# OBC_My_FPGA.net
KiCad netlist of a schematic drawn in Altium Designer
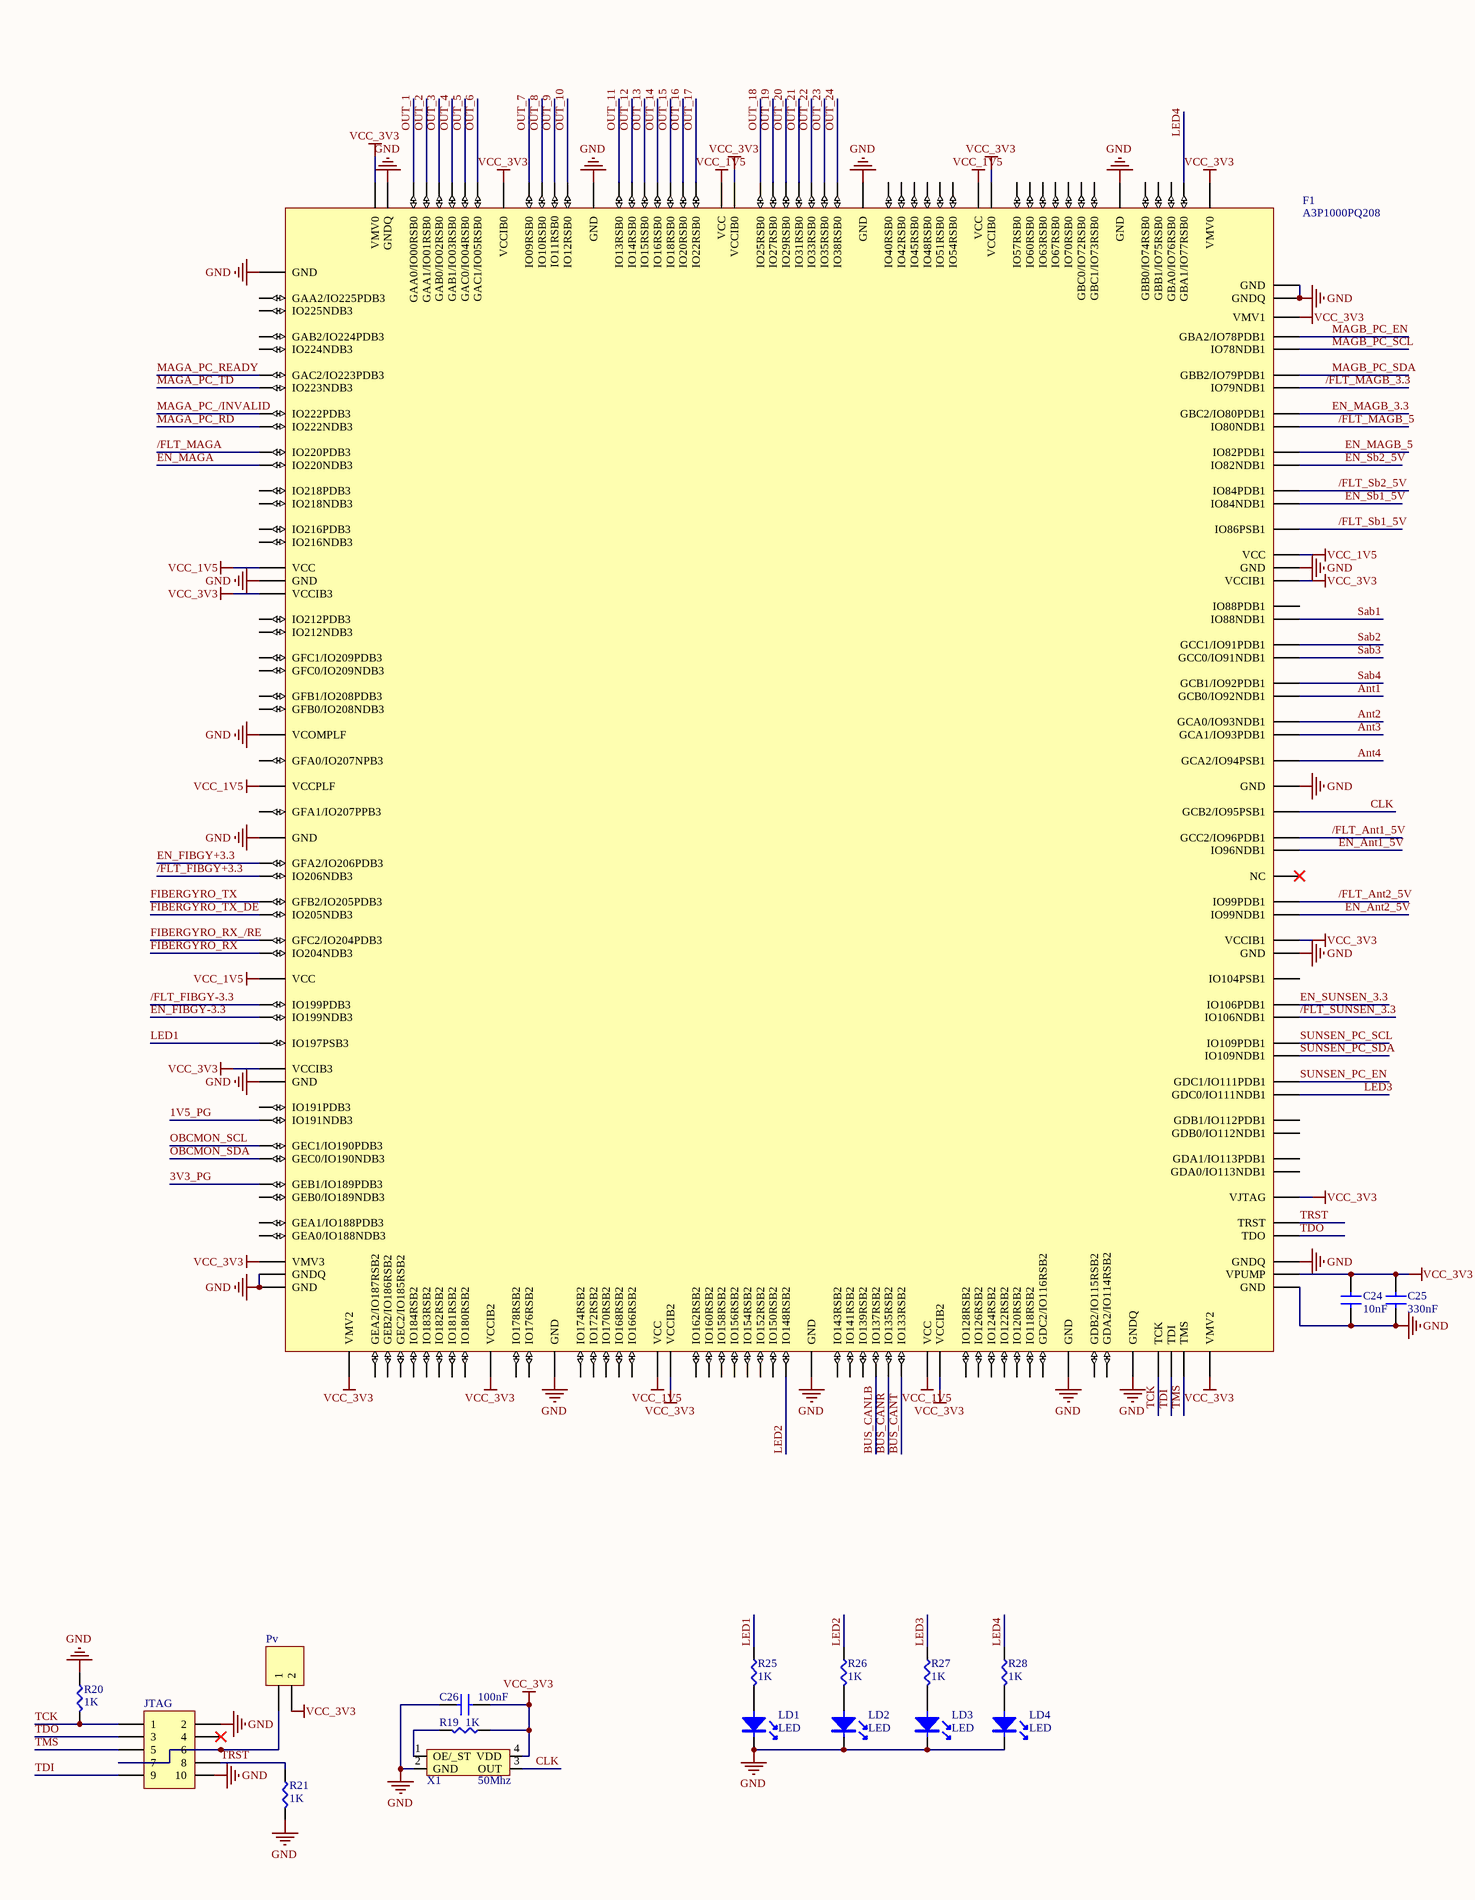
[diagram p0: OBC_My_FPGA.SchDoc, left]
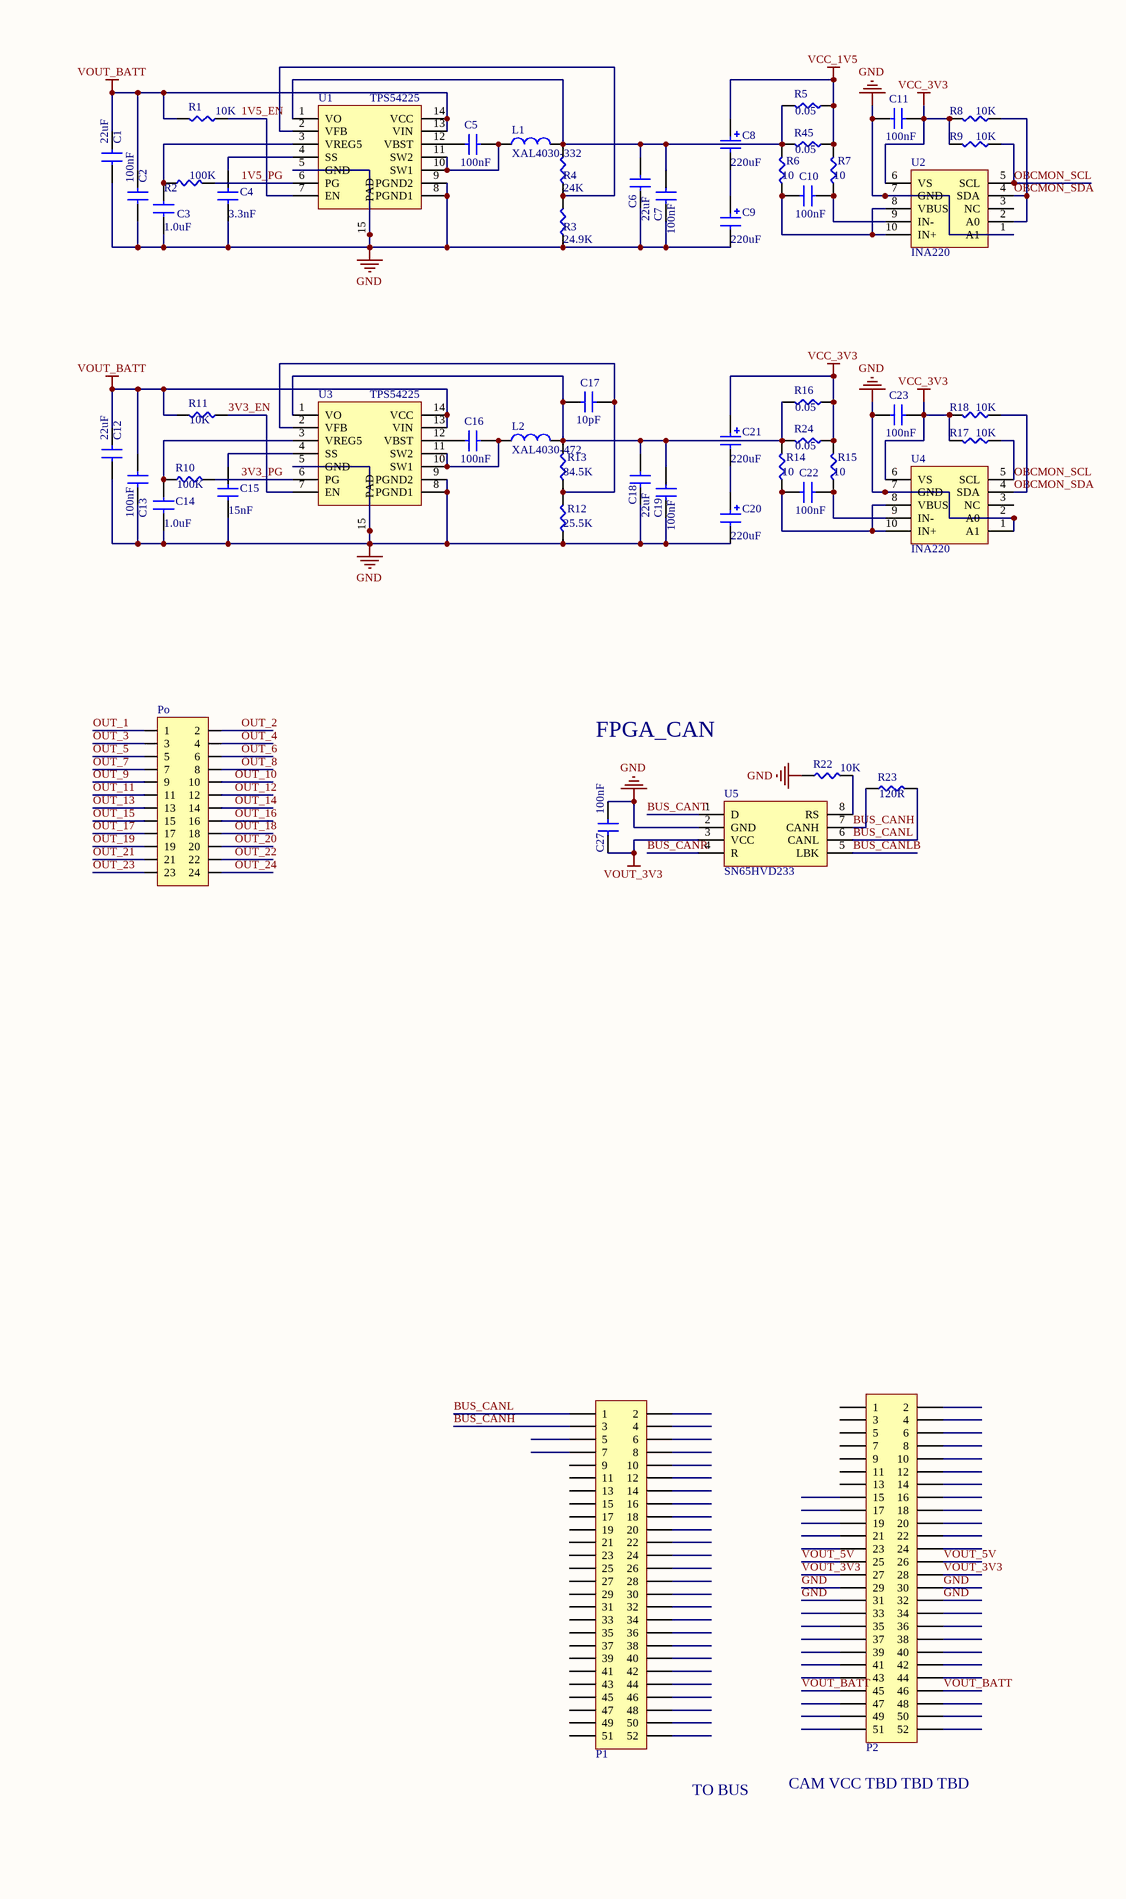
[diagram p1: OBC_My_FPGA.SchDoc, right]

(export (version "E")
  (design (tool "Eeschema 10.0.6"))
  (components
    (comp (ref "C1")
      (value "22uF")
      (footprint "1210(3225)-C-IPC")
      (description "Nonpolarized Capacitor (Surface Mount)")
      (libsource (lib "General Components") (part "Cap_1"))
    )
    (comp (ref "C2")
      (value "100nF")
      (footprint "0805(2012)-C-IPC")
      (description "Nonpolarized Capacitor (Surface Mount)")
      (libsource (lib "General Components") (part "Cap_1"))
    )
    (comp (ref "C3")
      (value "1.0uF")
      (footprint "0603(1608)-C-IPC")
      (description "Nonpolarized Capacitor (Surface Mount)")
      (libsource (lib "General Components") (part "Cap_1"))
    )
    (comp (ref "C4")
      (value "3.3nF")
      (footprint "0603(1608)-C-IPC")
      (description "Nonpolarized Capacitor (Surface Mount)")
      (libsource (lib "General Components") (part "Cap_1"))
    )
    (comp (ref "C5")
      (value "100nF")
      (footprint "0603(1608)-C-IPC")
      (description "Nonpolarized Capacitor (Surface Mount)")
      (libsource (lib "General Components") (part "Cap_1"))
    )
    (comp (ref "C6")
      (value "22uF")
      (footprint "1210(3225)-C-IPC")
      (description "Nonpolarized Capacitor (Surface Mount)")
      (libsource (lib "General Components") (part "Cap_1"))
    )
    (comp (ref "C7")
      (value "100nF")
      (footprint "0805(2012)-C-IPC")
      (description "Nonpolarized Capacitor (Surface Mount)")
      (libsource (lib "General Components") (part "Cap_1"))
    )
    (comp (ref "C8")
      (value "220uF")
      (footprint "TanCap-D(7343)-C-IPC")
      (description "Polarized Capacitor (Surface Mount)")
      (libsource (lib "General Components") (part "Cap Pol_1"))
    )
    (comp (ref "C9")
      (value "220uF")
      (footprint "TanCap-D(7343)-C-IPC")
      (description "Polarized Capacitor (Surface Mount)")
      (libsource (lib "General Components") (part "Cap Pol_1"))
    )
    (comp (ref "C10")
      (value "100nF")
      (footprint "0603(1608)-C-IPC")
      (description "Nonpolarized Capacitor (Surface Mount)")
      (libsource (lib "General Components") (part "Cap_1"))
    )
    (comp (ref "C11")
      (value "100nF")
      (footprint "0603(1608)-C-IPC")
      (description "Nonpolarized Capacitor (Surface Mount)")
      (libsource (lib "General Components") (part "Cap_1"))
    )
    (comp (ref "C12")
      (value "22uF")
      (footprint "1210(3225)-C-IPC")
      (description "Nonpolarized Capacitor (Surface Mount)")
      (libsource (lib "General Components") (part "Cap_1"))
    )
    (comp (ref "C13")
      (value "100nF")
      (footprint "0805(2012)-C-IPC")
      (description "Nonpolarized Capacitor (Surface Mount)")
      (libsource (lib "General Components") (part "Cap_1"))
    )
    (comp (ref "C14")
      (value "1.0uF")
      (footprint "0603(1608)-C-IPC")
      (description "Nonpolarized Capacitor (Surface Mount)")
      (libsource (lib "General Components") (part "Cap_1"))
    )
    (comp (ref "C15")
      (value "15nF")
      (footprint "0603(1608)-C-IPC")
      (description "Nonpolarized Capacitor (Surface Mount)")
      (libsource (lib "General Components") (part "Cap_1"))
    )
    (comp (ref "C16")
      (value "100nF")
      (footprint "0603(1608)-C-IPC")
      (description "Nonpolarized Capacitor (Surface Mount)")
      (libsource (lib "General Components") (part "Cap_1"))
    )
    (comp (ref "C17")
      (value "10pF")
      (footprint "0603(1608)-C-IPC")
      (description "Nonpolarized Capacitor (Surface Mount)")
      (libsource (lib "General Components") (part "Cap_1"))
    )
    (comp (ref "C18")
      (value "22uF")
      (footprint "1210(3225)-C-IPC")
      (description "Nonpolarized Capacitor (Surface Mount)")
      (libsource (lib "General Components") (part "Cap_1"))
    )
    (comp (ref "C19")
      (value "100nF")
      (footprint "0805(2012)-C-IPC")
      (description "Nonpolarized Capacitor (Surface Mount)")
      (libsource (lib "General Components") (part "Cap_1"))
    )
    (comp (ref "C20")
      (value "220uF")
      (footprint "TanCap-D(7343)-C-IPC")
      (description "Polarized Capacitor (Surface Mount)")
      (libsource (lib "General Components") (part "Cap Pol_1"))
    )
    (comp (ref "C21")
      (value "220uF")
      (footprint "TanCap-D(7343)-C-IPC")
      (description "Polarized Capacitor (Surface Mount)")
      (libsource (lib "General Components") (part "Cap Pol_1"))
    )
    (comp (ref "C22")
      (value "100nF")
      (footprint "0603(1608)-C-IPC")
      (description "Nonpolarized Capacitor (Surface Mount)")
      (libsource (lib "General Components") (part "Cap_1"))
    )
    (comp (ref "C23")
      (value "100nF")
      (footprint "0603(1608)-C-IPC")
      (description "Nonpolarized Capacitor (Surface Mount)")
      (libsource (lib "General Components") (part "Cap_1"))
    )
    (comp (ref "C24")
      (value "10nF")
      (footprint "0603(1608)-C-IPC")
      (description "Nonpolarized Capacitor (Surface Mount)")
      (libsource (lib "General Components") (part "Cap_1"))
    )
    (comp (ref "C25")
      (value "330nF")
      (footprint "0603(1608)-C-IPC")
      (description "Nonpolarized Capacitor (Surface Mount)")
      (libsource (lib "General Components") (part "Cap_1"))
    )
    (comp (ref "C26")
      (value "100nF")
      (footprint "0603(1608)-C-IPC")
      (description "Nonpolarized Capacitor (Surface Mount)")
      (libsource (lib "General Components") (part "Cap_1"))
    )
    (comp (ref "C27")
      (value "100nF")
      (footprint "0603(1608)-C-IPC")
      (description "Nonpolarized Capacitor (Surface Mount)")
      (libsource (lib "General Components") (part "Cap_1"))
    )
    (comp (ref "F1")
      (value "A3P1000PQ208")
      (footprint "SQFP50P3060X3060X410-208N")
      (description "ProASIC3 Flash Family FPGAs")
      (libsource (lib "Microsemi Series") (part "A3P100PQ208"))
    )
    (comp (ref "JTAG")
      (value "Header 5X2")
      (footprint "HDR2X5")
      (description "Header, 5-Pin, Dual row")
      (fields (field (name "PUBLISHER") "Altium Limited"))
      (libsource (lib "Miscellaneous Connectors") (part "Header 5X2"))
    )
    (comp (ref "L1")
      (value "XAL4030-332")
      (footprint "Inductor-CoilCraft-XAL40xx")
      (description "Inductor")
      (libsource (lib "General Components") (part "Inductor_1"))
    )
    (comp (ref "L2")
      (value "XAL4030-472")
      (footprint "Inductor-CoilCraft-XAL40xx")
      (description "Inductor")
      (libsource (lib "General Components") (part "Inductor_1"))
    )
    (comp (ref "LD1")
      (value "LED")
      (footprint "0603(1608)-C-IPC")
      (libsource (lib "General Components") (part "LED"))
    )
    (comp (ref "LD2")
      (value "LED")
      (footprint "0603(1608)-C-IPC")
      (libsource (lib "General Components") (part "LED"))
    )
    (comp (ref "LD3")
      (value "LED")
      (footprint "0603(1608)-C-IPC")
      (libsource (lib "General Components") (part "LED"))
    )
    (comp (ref "LD4")
      (value "LED")
      (footprint "0603(1608)-C-IPC")
      (libsource (lib "General Components") (part "LED"))
    )
    (comp (ref "P1")
      (value "Header 26X2H")
      (footprint "DIP 26x2-2.54mm")
      (description "Header, 26-Pin, Dual row, Right Angle")
      (libsource (lib "Header") (part "Header 26X2H"))
    )
    (comp (ref "P2")
      (value "Header 26X2H")
      (footprint "DIP 26x2-2.54mm")
      (description "Header, 26-Pin, Dual row, Right Angle")
      (libsource (lib "Header") (part "Header 26X2H"))
    )
    (comp (ref "Po")
      (value "Header 12x2")
      (footprint "DIP 12x2-2.54mm")
      (libsource (lib "Header") (part "Header 12x2"))
    )
    (comp (ref "Pv")
      (value "Header 2")
      (footprint "HDR1X2")
      (description "Header, 2-Pin")
      (fields (field (name "PUBLISHER") "Altium Limited"))
      (libsource (lib "Miscellaneous Connectors") (part "Header 2"))
    )
    (comp (ref "R1")
      (value "10K")
      (footprint "0603(1608)-R-IPC")
      (description "Resistor")
      (libsource (lib "General Components") (part "Res_1"))
    )
    (comp (ref "R2")
      (value "100K")
      (footprint "0603(1608)-R-IPC")
      (description "Resistor")
      (libsource (lib "General Components") (part "Res_1"))
    )
    (comp (ref "R3")
      (value "24.9K")
      (footprint "0603(1608)-R-IPC")
      (description "Resistor")
      (libsource (lib "General Components") (part "Res_1"))
    )
    (comp (ref "R4")
      (value "24K")
      (footprint "0603(1608)-R-IPC")
      (description "Resistor")
      (libsource (lib "General Components") (part "Res_1"))
    )
    (comp (ref "R5")
      (value "0.05")
      (footprint "1206(3216)-R-IPC")
      (description "Resistor")
      (libsource (lib "General Components") (part "Res_1"))
    )
    (comp (ref "R6")
      (value "10")
      (footprint "0603(1608)-R-IPC")
      (description "Resistor")
      (libsource (lib "General Components") (part "Res_1"))
    )
    (comp (ref "R7")
      (value "10")
      (footprint "0603(1608)-R-IPC")
      (description "Resistor")
      (libsource (lib "General Components") (part "Res_1"))
    )
    (comp (ref "R8")
      (value "10K")
      (footprint "0603(1608)-R-IPC")
      (description "Resistor")
      (libsource (lib "General Components") (part "Res_1"))
    )
    (comp (ref "R9")
      (value "10K")
      (footprint "0603(1608)-R-IPC")
      (description "Resistor")
      (libsource (lib "General Components") (part "Res_1"))
    )
    (comp (ref "R10")
      (value "100K")
      (footprint "0603(1608)-R-IPC")
      (description "Resistor")
      (libsource (lib "General Components") (part "Res_1"))
    )
    (comp (ref "R11")
      (value "10K")
      (footprint "0603(1608)-R-IPC")
      (description "Resistor")
      (libsource (lib "General Components") (part "Res_1"))
    )
    (comp (ref "R12")
      (value "25.5K")
      (footprint "0603(1608)-R-IPC")
      (description "Resistor")
      (libsource (lib "General Components") (part "Res_1"))
    )
    (comp (ref "R13")
      (value "84.5K")
      (footprint "0603(1608)-R-IPC")
      (description "Resistor")
      (libsource (lib "General Components") (part "Res_1"))
    )
    (comp (ref "R14")
      (value "10")
      (footprint "0603(1608)-R-IPC")
      (description "Resistor")
      (libsource (lib "General Components") (part "Res_1"))
    )
    (comp (ref "R15")
      (value "10")
      (footprint "0603(1608)-R-IPC")
      (description "Resistor")
      (libsource (lib "General Components") (part "Res_1"))
    )
    (comp (ref "R16")
      (value "0.05")
      (footprint "1206(3216)-R-IPC")
      (description "Resistor")
      (libsource (lib "General Components") (part "Res_1"))
    )
    (comp (ref "R17")
      (value "10K")
      (footprint "0603(1608)-R-IPC")
      (description "Resistor")
      (libsource (lib "General Components") (part "Res_1"))
    )
    (comp (ref "R18")
      (value "10K")
      (footprint "0603(1608)-R-IPC")
      (description "Resistor")
      (libsource (lib "General Components") (part "Res_1"))
    )
    (comp (ref "R19")
      (value "1K")
      (footprint "0603(1608)-R-IPC")
      (description "Resistor")
      (libsource (lib "General Components") (part "Res_1"))
    )
    (comp (ref "R20")
      (value "1K")
      (footprint "0603(1608)-R-IPC")
      (description "Resistor")
      (libsource (lib "General Components") (part "Res_1"))
    )
    (comp (ref "R21")
      (value "1K")
      (footprint "0603(1608)-R-IPC")
      (description "Resistor")
      (libsource (lib "General Components") (part "Res_1"))
    )
    (comp (ref "R22")
      (value "10K")
      (footprint "0603(1608)-R-IPC")
      (description "Resistor")
      (libsource (lib "General Components") (part "Res_1"))
    )
    (comp (ref "R23")
      (value "120R")
      (footprint "0603(1608)-R-IPC")
      (description "Resistor")
      (fields (field (name "Comment") "120"))
      (libsource (lib "General Components") (part "Res_1"))
    )
    (comp (ref "R24")
      (value "0.05")
      (footprint "1206(3216)-R-IPC")
      (description "Resistor")
      (libsource (lib "General Components") (part "Res_1"))
    )
    (comp (ref "R25")
      (value "1K")
      (footprint "0603(1608)-R-IPC")
      (description "Resistor")
      (libsource (lib "General Components") (part "Res_1"))
    )
    (comp (ref "R26")
      (value "1K")
      (footprint "0603(1608)-R-IPC")
      (description "Resistor")
      (libsource (lib "General Components") (part "Res_1"))
    )
    (comp (ref "R27")
      (value "1K")
      (footprint "0603(1608)-R-IPC")
      (description "Resistor")
      (libsource (lib "General Components") (part "Res_1"))
    )
    (comp (ref "R28")
      (value "1K")
      (footprint "0603(1608)-R-IPC")
      (description "Resistor")
      (libsource (lib "General Components") (part "Res_1"))
    )
    (comp (ref "R45")
      (value "0.05")
      (footprint "1206(3216)-R-IPC")
      (description "Resistor")
      (libsource (lib "General Components") (part "Res_1"))
    )
    (comp (ref "U1")
      (value "TPS54225")
      (footprint "TSSOP-14-4.4x5-0.65-w.TP-IPC")
      (description "4.5V to 18V Input, 2-A Synchronous Step-Down SWIFT Converter")
      (libsource (lib "TI Series") (part "TPS54225"))
    )
    (comp (ref "U2")
      (value "INA220")
      (footprint "TSSOP-10-3x3-IPC")
      (description "High- or Low-Side, Bidirectional Current and Power Monitor With Two-Wire Interface")
      (libsource (lib "TI Series") (part "INA220"))
    )
    (comp (ref "U3")
      (value "TPS54225")
      (footprint "TSSOP-14-4.4x5-0.65-w.TP-IPC")
      (description "4.5V to 18V Input, 2-A Synchronous Step-Down SWIFT Converter")
      (libsource (lib "TI Series") (part "TPS54225"))
    )
    (comp (ref "U4")
      (value "INA220")
      (footprint "TSSOP-10-3x3-IPC")
      (description "High- or Low-Side, Bidirectional Current and Power Monitor With Two-Wire Interface")
      (libsource (lib "TI Series") (part "INA220"))
    )
    (comp (ref "U5")
      (value "SN65HVD233")
      (footprint "SOP-8-3.9x4.9-IPC")
      (description "3.3-V CAN Bus Transceivers")
      (libsource (lib "TI Series") (part "SN65HVD233"))
    )
    (comp (ref "X1")
      (value "50Mhz")
      (footprint "LC-SMD-3225_4P")
      (description "Standard Frequency Oscillator SiT1602")
      (libsource (lib "General Components") (part "SiT1602"))
    )
  )
  (nets
    (net (code "1") (name "/1V5_EN") (class "Default")
      (node (ref "R1") (pin "1") (pinfunction "1_1") (pintype "passive"))
      (node (ref "U1") (pin "7") (pinfunction "EN_7") (pintype "passive"))
    )
    (net (code "2") (name "/1V5_PG") (class "Default")
      (node (ref "F1") (pin "43") (pinfunction "IO191NDB3_43") (pintype "bidirectional"))
      (node (ref "R2") (pin "2") (pinfunction "2_2") (pintype "passive"))
      (node (ref "U1") (pin "6") (pinfunction "PG_6") (pintype "passive"))
    )
    (net (code "3") (name "/3V3_EN") (class "Default")
      (node (ref "R11") (pin "1") (pinfunction "1_1") (pintype "passive"))
      (node (ref "U3") (pin "7") (pinfunction "EN_7") (pintype "passive"))
    )
    (net (code "4") (name "/3V3_PG") (class "Default")
      (node (ref "F1") (pin "46") (pinfunction "GEB1/IO189PDB3_46") (pintype "bidirectional"))
      (node (ref "R10") (pin "2") (pinfunction "2_2") (pintype "passive"))
      (node (ref "U3") (pin "6") (pinfunction "PG_6") (pintype "passive"))
    )
    (net (code "5") (name "/Ant1") (class "Default")
      (node (ref "F1") (pin "134") (pinfunction "GCB0/IO92NDB1_134") (pintype "power_in"))
    )
    (net (code "6") (name "/Ant2") (class "Default")
      (node (ref "F1") (pin "133") (pinfunction "GCA0/IO93NDB1_133") (pintype "power_in"))
    )
    (net (code "7") (name "/Ant3") (class "Default")
      (node (ref "F1") (pin "132") (pinfunction "GCA1/IO93PDB1_132") (pintype "power_in"))
    )
    (net (code "8") (name "/Ant4") (class "Default")
      (node (ref "F1") (pin "131") (pinfunction "GCA2/IO94PSB1_131") (pintype "power_in"))
    )
    (net (code "9") (name "/BUS_CANH") (class "Default")
      (node (ref "P1") (pin "3") (pinfunction "3_3") (pintype "passive"))
      (node (ref "R23") (pin "1") (pinfunction "1_1") (pintype "passive"))
      (node (ref "U5") (pin "7") (pinfunction "CANH_7") (pintype "passive"))
    )
    (net (code "10") (name "/BUS_CANL") (class "Default")
      (node (ref "P1") (pin "1") (pinfunction "1_1") (pintype "passive"))
      (node (ref "R23") (pin "2") (pinfunction "2_2") (pintype "passive"))
      (node (ref "U5") (pin "6") (pinfunction "CANL_6") (pintype "passive"))
    )
    (net (code "11") (name "/BUS_CANLB") (class "Default")
      (node (ref "F1") (pin "85") (pinfunction "IO137RSB2_85") (pintype "bidirectional"))
      (node (ref "U5") (pin "5") (pinfunction "LBK_5") (pintype "passive"))
    )
    (net (code "12") (name "/BUS_CANR") (class "Default")
      (node (ref "F1") (pin "86") (pinfunction "IO135RSB2_86") (pintype "bidirectional"))
      (node (ref "U5") (pin "4") (pinfunction "R_4") (pintype "passive"))
    )
    (net (code "13") (name "/BUS_CANT") (class "Default")
      (node (ref "F1") (pin "87") (pinfunction "IO133RSB2_87") (pintype "bidirectional"))
      (node (ref "U5") (pin "1") (pinfunction "D_1") (pintype "passive"))
    )
    (net (code "14") (name "/CLK") (class "Default")
      (node (ref "F1") (pin "129") (pinfunction "GCB2/IO95PSB1_129") (pintype "power_in"))
      (node (ref "X1") (pin "3") (pinfunction "OUT_3") (pintype "passive"))
    )
    (net (code "15") (name "/EN_Ant1_5V") (class "Default")
      (node (ref "F1") (pin "127") (pinfunction "IO96NDB1_127") (pintype "power_in"))
    )
    (net (code "16") (name "/EN_Ant2_5V") (class "Default")
      (node (ref "F1") (pin "124") (pinfunction "IO99NDB1_124") (pintype "power_in"))
    )
    (net (code "17") (name "/EN_FIBGY+3.3") (class "Default")
      (node (ref "F1") (pin "30") (pinfunction "GFA2/IO206PDB3_30") (pintype "bidirectional"))
    )
    (net (code "18") (name "/EN_FIBGY-3.3") (class "Default")
      (node (ref "F1") (pin "38") (pinfunction "IO199NDB3_38") (pintype "bidirectional"))
    )
    (net (code "19") (name "/EN_MAGA") (class "Default")
      (node (ref "F1") (pin "11") (pinfunction "IO220NDB3_11") (pintype "bidirectional"))
    )
    (net (code "20") (name "/EN_MAGB_3.3") (class "Default")
      (node (ref "F1") (pin "149") (pinfunction "GBC2/IO80PDB1_149") (pintype "passive"))
    )
    (net (code "21") (name "/EN_MAGB_5") (class "Default")
      (node (ref "F1") (pin "147") (pinfunction "IO82PDB1_147") (pintype "passive"))
    )
    (net (code "22") (name "/EN_SUNSEN_3.3") (class "Default")
      (node (ref "F1") (pin "120") (pinfunction "IO106PDB1_120") (pintype "power_in"))
    )
    (net (code "23") (name "/EN_Sb1_5V") (class "Default")
      (node (ref "F1") (pin "144") (pinfunction "IO84NDB1_144") (pintype "passive"))
    )
    (net (code "24") (name "/EN_Sb2_5V") (class "Default")
      (node (ref "F1") (pin "146") (pinfunction "IO82NDB1_146") (pintype "passive"))
    )
    (net (code "25") (name "/FIBERGYRO_RX") (class "Default")
      (node (ref "F1") (pin "35") (pinfunction "IO204NDB3_35") (pintype "bidirectional"))
    )
    (net (code "26") (name "/FIBERGYRO_RX_{slash}RE") (class "Default")
      (node (ref "F1") (pin "34") (pinfunction "GFC2/IO204PDB3_34") (pintype "bidirectional"))
    )
    (net (code "27") (name "/FIBERGYRO_TX") (class "Default")
      (node (ref "F1") (pin "32") (pinfunction "GFB2/IO205PDB3_32") (pintype "bidirectional"))
    )
    (net (code "28") (name "/FIBERGYRO_TX_DE") (class "Default")
      (node (ref "F1") (pin "33") (pinfunction "IO205NDB3_33") (pintype "bidirectional"))
    )
    (net (code "29") (name "/LED1") (class "Default")
      (node (ref "F1") (pin "39") (pinfunction "IO197PSB3_39") (pintype "bidirectional"))
      (node (ref "R25") (pin "1") (pinfunction "1_1") (pintype "passive"))
    )
    (net (code "30") (name "/LED2") (class "Default")
      (node (ref "F1") (pin "80") (pinfunction "IO148RSB2_80") (pintype "bidirectional"))
      (node (ref "R26") (pin "1") (pinfunction "1_1") (pintype "passive"))
    )
    (net (code "31") (name "/LED3") (class "Default")
      (node (ref "F1") (pin "115") (pinfunction "GDC0/IO111NDB1_115") (pintype "power_in"))
      (node (ref "R27") (pin "1") (pinfunction "1_1") (pintype "passive"))
    )
    (net (code "32") (name "/LED4") (class "Default")
      (node (ref "F1") (pin "158") (pinfunction "GBA1/IO77RSB0_158") (pintype "bidirectional"))
      (node (ref "R28") (pin "1") (pinfunction "1_1") (pintype "passive"))
    )
    (net (code "33") (name "/MAGA_PC_RD") (class "Default")
      (node (ref "F1") (pin "9") (pinfunction "IO222NDB3_9") (pintype "bidirectional"))
    )
    (net (code "34") (name "/MAGA_PC_READY") (class "Default")
      (node (ref "F1") (pin "6") (pinfunction "GAC2/IO223PDB3_6") (pintype "bidirectional"))
    )
    (net (code "35") (name "/MAGA_PC_TD") (class "Default")
      (node (ref "F1") (pin "7") (pinfunction "IO223NDB3_7") (pintype "bidirectional"))
    )
    (net (code "36") (name "/MAGA_PC_{slash}INVALID") (class "Default")
      (node (ref "F1") (pin "8") (pinfunction "IO222PDB3_8") (pintype "bidirectional"))
    )
    (net (code "37") (name "/MAGB_PC_EN") (class "Default")
      (node (ref "F1") (pin "153") (pinfunction "GBA2/IO78PDB1_153") (pintype "passive"))
    )
    (net (code "38") (name "/MAGB_PC_SCL") (class "Default")
      (node (ref "F1") (pin "152") (pinfunction "IO78NDB1_152") (pintype "passive"))
    )
    (net (code "39") (name "/MAGB_PC_SDA") (class "Default")
      (node (ref "F1") (pin "151") (pinfunction "GBB2/IO79PDB1_151") (pintype "passive"))
    )
    (net (code "40") (name "/OBCMON_SCL") (class "Default")
      (node (ref "F1") (pin "44") (pinfunction "GEC1/IO190PDB3_44") (pintype "bidirectional"))
      (node (ref "R17") (pin "1") (pinfunction "1_1") (pintype "passive"))
      (node (ref "R9") (pin "1") (pinfunction "1_1") (pintype "passive"))
      (node (ref "U2") (pin "5") (pinfunction "SCL_5") (pintype "passive"))
      (node (ref "U4") (pin "5") (pinfunction "SCL_5") (pintype "passive"))
    )
    (net (code "41") (name "/OBCMON_SDA") (class "Default")
      (node (ref "F1") (pin "45") (pinfunction "GEC0/IO190NDB3_45") (pintype "bidirectional"))
      (node (ref "R18") (pin "1") (pinfunction "1_1") (pintype "passive"))
      (node (ref "R8") (pin "1") (pinfunction "1_1") (pintype "passive"))
      (node (ref "U2") (pin "2") (pinfunction "A0_2") (pintype "passive"))
      (node (ref "U2") (pin "4") (pinfunction "SDA_4") (pintype "passive"))
      (node (ref "U4") (pin "4") (pinfunction "SDA_4") (pintype "passive"))
    )
    (net (code "42") (name "/OUT_1") (class "Default")
      (node (ref "F1") (pin "206") (pinfunction "GAA0/IO00RSB0_206") (pintype "bidirectional"))
      (node (ref "Po") (pin "1") (pinfunction "1_1") (pintype "passive"))
    )
    (net (code "43") (name "/OUT_2") (class "Default")
      (node (ref "F1") (pin "205") (pinfunction "GAA1/IO01RSB0_205") (pintype "bidirectional"))
      (node (ref "Po") (pin "2") (pinfunction "2_2") (pintype "passive"))
    )
    (net (code "44") (name "/OUT_3") (class "Default")
      (node (ref "F1") (pin "204") (pinfunction "GAB0/IO02RSB0_204") (pintype "bidirectional"))
      (node (ref "Po") (pin "3") (pinfunction "3_3") (pintype "passive"))
    )
    (net (code "45") (name "/OUT_4") (class "Default")
      (node (ref "F1") (pin "203") (pinfunction "GAB1/IO03RSB0_203") (pintype "bidirectional"))
      (node (ref "Po") (pin "4") (pinfunction "4_4") (pintype "passive"))
    )
    (net (code "46") (name "/OUT_5") (class "Default")
      (node (ref "F1") (pin "202") (pinfunction "GAC0/IO04RSB0_202") (pintype "bidirectional"))
      (node (ref "Po") (pin "5") (pinfunction "5_5") (pintype "passive"))
    )
    (net (code "47") (name "/OUT_6") (class "Default")
      (node (ref "F1") (pin "201") (pinfunction "GAC1/IO05RSB0_201") (pintype "bidirectional"))
      (node (ref "Po") (pin "6") (pinfunction "6_6") (pintype "passive"))
    )
    (net (code "48") (name "/OUT_7") (class "Default")
      (node (ref "F1") (pin "199") (pinfunction "IO09RSB0_199") (pintype "bidirectional"))
      (node (ref "Po") (pin "7") (pinfunction "7_7") (pintype "passive"))
    )
    (net (code "49") (name "/OUT_8") (class "Default")
      (node (ref "F1") (pin "198") (pinfunction "IO10RSB0_198") (pintype "bidirectional"))
      (node (ref "Po") (pin "8") (pinfunction "8_8") (pintype "passive"))
    )
    (net (code "50") (name "/OUT_9") (class "Default")
      (node (ref "F1") (pin "197") (pinfunction "IO11RSB0_197") (pintype "bidirectional"))
      (node (ref "Po") (pin "9") (pinfunction "9_9") (pintype "passive"))
    )
    (net (code "51") (name "/OUT_10") (class "Default")
      (node (ref "F1") (pin "196") (pinfunction "IO12RSB0_196") (pintype "bidirectional"))
      (node (ref "Po") (pin "10") (pinfunction "10_10") (pintype "passive"))
    )
    (net (code "52") (name "/OUT_11") (class "Default")
      (node (ref "F1") (pin "194") (pinfunction "IO13RSB0_194") (pintype "bidirectional"))
      (node (ref "Po") (pin "11") (pinfunction "11_11") (pintype "passive"))
    )
    (net (code "53") (name "/OUT_12") (class "Default")
      (node (ref "F1") (pin "193") (pinfunction "IO14RSB0_193") (pintype "bidirectional"))
      (node (ref "Po") (pin "12") (pinfunction "12_12") (pintype "passive"))
    )
    (net (code "54") (name "/OUT_13") (class "Default")
      (node (ref "F1") (pin "192") (pinfunction "IO15RSB0_192") (pintype "bidirectional"))
      (node (ref "Po") (pin "13") (pinfunction "13_13") (pintype "passive"))
    )
    (net (code "55") (name "/OUT_14") (class "Default")
      (node (ref "F1") (pin "191") (pinfunction "IO16RSB0_191") (pintype "bidirectional"))
      (node (ref "Po") (pin "14") (pinfunction "14_14") (pintype "passive"))
    )
    (net (code "56") (name "/OUT_15") (class "Default")
      (node (ref "F1") (pin "190") (pinfunction "IO18RSB0_190") (pintype "bidirectional"))
      (node (ref "Po") (pin "15") (pinfunction "15_15") (pintype "passive"))
    )
    (net (code "57") (name "/OUT_16") (class "Default")
      (node (ref "F1") (pin "189") (pinfunction "IO20RSB0_189") (pintype "bidirectional"))
      (node (ref "Po") (pin "16") (pinfunction "16_16") (pintype "passive"))
    )
    (net (code "58") (name "/OUT_17") (class "Default")
      (node (ref "F1") (pin "188") (pinfunction "IO22RSB0_188") (pintype "bidirectional"))
      (node (ref "Po") (pin "17") (pinfunction "17_17") (pintype "passive"))
    )
    (net (code "59") (name "/OUT_18") (class "Default")
      (node (ref "F1") (pin "185") (pinfunction "IO25RSB0_185") (pintype "bidirectional"))
      (node (ref "Po") (pin "18") (pinfunction "18_18") (pintype "passive"))
    )
    (net (code "60") (name "/OUT_19") (class "Default")
      (node (ref "F1") (pin "184") (pinfunction "IO27RSB0_184") (pintype "bidirectional"))
      (node (ref "Po") (pin "19") (pinfunction "19_19") (pintype "passive"))
    )
    (net (code "61") (name "/OUT_20") (class "Default")
      (node (ref "F1") (pin "183") (pinfunction "IO29RSB0_183") (pintype "bidirectional"))
      (node (ref "Po") (pin "20") (pinfunction "20_20") (pintype "passive"))
    )
    (net (code "62") (name "/OUT_21") (class "Default")
      (node (ref "F1") (pin "182") (pinfunction "IO31RSB0_182") (pintype "bidirectional"))
      (node (ref "Po") (pin "21") (pinfunction "21_21") (pintype "passive"))
    )
    (net (code "63") (name "/OUT_22") (class "Default")
      (node (ref "F1") (pin "181") (pinfunction "IO33RSB0_181") (pintype "bidirectional"))
      (node (ref "Po") (pin "22") (pinfunction "22_22") (pintype "passive"))
    )
    (net (code "64") (name "/OUT_23") (class "Default")
      (node (ref "F1") (pin "180") (pinfunction "IO35RSB0_180") (pintype "bidirectional"))
      (node (ref "Po") (pin "23") (pinfunction "23_23") (pintype "passive"))
    )
    (net (code "65") (name "/OUT_24") (class "Default")
      (node (ref "F1") (pin "179") (pinfunction "IO38RSB0_179") (pintype "bidirectional"))
      (node (ref "Po") (pin "24") (pinfunction "24_24") (pintype "passive"))
    )
    (net (code "66") (name "/SUNSEN_PC_EN") (class "Default")
      (node (ref "F1") (pin "116") (pinfunction "GDC1/IO111PDB1_116") (pintype "power_in"))
    )
    (net (code "67") (name "/SUNSEN_PC_SCL") (class "Default")
      (node (ref "F1") (pin "118") (pinfunction "IO109PDB1_118") (pintype "power_in"))
    )
    (net (code "68") (name "/SUNSEN_PC_SDA") (class "Default")
      (node (ref "F1") (pin "117") (pinfunction "IO109NDB1_117") (pintype "power_in"))
    )
    (net (code "69") (name "/Sab1") (class "Default")
      (node (ref "F1") (pin "138") (pinfunction "IO88NDB1_138") (pintype "power_in"))
    )
    (net (code "70") (name "/Sab2") (class "Default")
      (node (ref "F1") (pin "137") (pinfunction "GCC1/IO91PDB1_137") (pintype "power_in"))
    )
    (net (code "71") (name "/Sab3") (class "Default")
      (node (ref "F1") (pin "136") (pinfunction "GCC0/IO91NDB1_136") (pintype "power_in"))
    )
    (net (code "72") (name "/Sab4") (class "Default")
      (node (ref "F1") (pin "135") (pinfunction "GCB1/IO92PDB1_135") (pintype "power_in"))
    )
    (net (code "73") (name "/TCK") (class "Default")
      (node (ref "F1") (pin "101") (pinfunction "TCK_101") (pintype "passive"))
      (node (ref "JTAG") (pin "1") (pinfunction "1_1") (pintype "passive"))
      (node (ref "R20") (pin "2") (pinfunction "2_2") (pintype "passive"))
    )
    (net (code "74") (name "/TDI") (class "Default")
      (node (ref "F1") (pin "102") (pinfunction "TDI_102") (pintype "passive"))
      (node (ref "JTAG") (pin "9") (pinfunction "9_9") (pintype "passive"))
    )
    (net (code "75") (name "/TDO") (class "Default")
      (node (ref "F1") (pin "108") (pinfunction "TDO_108") (pintype "power_in"))
      (node (ref "JTAG") (pin "3") (pinfunction "3_3") (pintype "passive"))
    )
    (net (code "76") (name "/TMS") (class "Default")
      (node (ref "F1") (pin "103") (pinfunction "TMS_103") (pintype "passive"))
      (node (ref "JTAG") (pin "5") (pinfunction "5_5") (pintype "passive"))
    )
    (net (code "77") (name "/TRST") (class "Default")
      (node (ref "F1") (pin "109") (pinfunction "TRST_109") (pintype "power_in"))
      (node (ref "JTAG") (pin "8") (pinfunction "8_8") (pintype "passive"))
      (node (ref "R21") (pin "1") (pinfunction "1_1") (pintype "passive"))
    )
    (net (code "78") (name "/VOUT_5V") (class "Default")
      (node (ref "P2") (pin "25") (pinfunction "25_25") (pintype "passive"))
      (node (ref "P2") (pin "26") (pinfunction "26_26") (pintype "passive"))
    )
    (net (code "79") (name "/{slash}FLT_Ant1_5V") (class "Default")
      (node (ref "F1") (pin "128") (pinfunction "GCC2/IO96PDB1_128") (pintype "power_in"))
    )
    (net (code "80") (name "/{slash}FLT_Ant2_5V") (class "Default")
      (node (ref "F1") (pin "125") (pinfunction "IO99PDB1_125") (pintype "power_in"))
    )
    (net (code "81") (name "/{slash}FLT_FIBGY+3.3") (class "Default")
      (node (ref "F1") (pin "31") (pinfunction "IO206NDB3_31") (pintype "bidirectional"))
    )
    (net (code "82") (name "/{slash}FLT_FIBGY-3.3") (class "Default")
      (node (ref "F1") (pin "37") (pinfunction "IO199PDB3_37") (pintype "bidirectional"))
    )
    (net (code "83") (name "/{slash}FLT_MAGA") (class "Default")
      (node (ref "F1") (pin "10") (pinfunction "IO220PDB3_10") (pintype "bidirectional"))
    )
    (net (code "84") (name "/{slash}FLT_MAGB_3.3") (class "Default")
      (node (ref "F1") (pin "150") (pinfunction "IO79NDB1_150") (pintype "passive"))
    )
    (net (code "85") (name "/{slash}FLT_MAGB_5") (class "Default")
      (node (ref "F1") (pin "148") (pinfunction "IO80NDB1_148") (pintype "passive"))
    )
    (net (code "86") (name "/{slash}FLT_SUNSEN_3.3") (class "Default")
      (node (ref "F1") (pin "119") (pinfunction "IO106NDB1_119") (pintype "power_in"))
    )
    (net (code "87") (name "/{slash}FLT_Sb1_5V") (class "Default")
      (node (ref "F1") (pin "143") (pinfunction "IO86PSB1_143") (pintype "passive"))
    )
    (net (code "88") (name "/{slash}FLT_Sb2_5V") (class "Default")
      (node (ref "F1") (pin "145") (pinfunction "IO84PDB1_145") (pintype "passive"))
    )
    (net (code "89") (name "GND") (class "Default")
      (node (ref "C1") (pin "2") (pinfunction "2_2") (pintype "passive"))
      (node (ref "C11") (pin "2") (pinfunction "2_2") (pintype "passive"))
      (node (ref "C12") (pin "2") (pinfunction "2_2") (pintype "passive"))
      (node (ref "C13") (pin "2") (pinfunction "2_2") (pintype "passive"))
      (node (ref "C14") (pin "1") (pinfunction "1_1") (pintype "passive"))
      (node (ref "C15") (pin "1") (pinfunction "1_1") (pintype "passive"))
      (node (ref "C18") (pin "2") (pinfunction "2_2") (pintype "passive"))
      (node (ref "C19") (pin "2") (pinfunction "2_2") (pintype "passive"))
      (node (ref "C2") (pin "2") (pinfunction "2_2") (pintype "passive"))
      (node (ref "C20") (pin "2") (pinfunction "2_2") (pintype "passive"))
      (node (ref "C23") (pin "2") (pinfunction "2_2") (pintype "passive"))
      (node (ref "C24") (pin "2") (pinfunction "2_2") (pintype "passive"))
      (node (ref "C25") (pin "2") (pinfunction "2_2") (pintype "passive"))
      (node (ref "C26") (pin "2") (pinfunction "2_2") (pintype "passive"))
      (node (ref "C27") (pin "2") (pinfunction "2_2") (pintype "passive"))
      (node (ref "C3") (pin "1") (pinfunction "1_1") (pintype "passive"))
      (node (ref "C4") (pin "1") (pinfunction "1_1") (pintype "passive"))
      (node (ref "C6") (pin "2") (pinfunction "2_2") (pintype "passive"))
      (node (ref "C7") (pin "2") (pinfunction "2_2") (pintype "passive"))
      (node (ref "C9") (pin "2") (pinfunction "2_2") (pintype "passive"))
      (node (ref "F1") (pin "1") (pinfunction "GND_1") (pintype "power_in"))
      (node (ref "F1") (pin "100") (pinfunction "GNDQ_100") (pintype "power_in"))
      (node (ref "F1") (pin "105") (pinfunction "GND_105") (pintype "power_in"))
      (node (ref "F1") (pin "107") (pinfunction "GNDQ_107") (pintype "power_in"))
      (node (ref "F1") (pin "122") (pinfunction "GND_122") (pintype "power_in"))
      (node (ref "F1") (pin "130") (pinfunction "GND_130") (pintype "passive"))
      (node (ref "F1") (pin "141") (pinfunction "GND_141") (pintype "passive"))
      (node (ref "F1") (pin "155") (pinfunction "GNDQ_155") (pintype "passive"))
      (node (ref "F1") (pin "156") (pinfunction "GND_156") (pintype "passive"))
      (node (ref "F1") (pin "162") (pinfunction "GND_162") (pintype "power_in"))
      (node (ref "F1") (pin "17") (pinfunction "GND_17") (pintype "power_in"))
      (node (ref "F1") (pin "178") (pinfunction "GND_178") (pintype "power_in"))
      (node (ref "F1") (pin "195") (pinfunction "GND_195") (pintype "power_in"))
      (node (ref "F1") (pin "207") (pinfunction "GNDQ_207") (pintype "power_in"))
      (node (ref "F1") (pin "25") (pinfunction "VCOMPLF_25") (pintype "power_in"))
      (node (ref "F1") (pin "29") (pinfunction "GND_29") (pintype "power_in"))
      (node (ref "F1") (pin "41") (pinfunction "GND_41") (pintype "power_in"))
      (node (ref "F1") (pin "51") (pinfunction "GNDQ_51") (pintype "power_in"))
      (node (ref "F1") (pin "52") (pinfunction "GND_52") (pintype "power_in"))
      (node (ref "F1") (pin "65") (pinfunction "GND_65") (pintype "power_in"))
      (node (ref "F1") (pin "81") (pinfunction "GND_81") (pintype "power_in"))
      (node (ref "F1") (pin "97") (pinfunction "GND_97") (pintype "power_in"))
      (node (ref "JTAG") (pin "2") (pinfunction "2_2") (pintype "passive"))
      (node (ref "LD1") (pin "2") (pinfunction "K_2") (pintype "passive"))
      (node (ref "LD2") (pin "2") (pinfunction "K_2") (pintype "passive"))
      (node (ref "LD3") (pin "2") (pinfunction "K_2") (pintype "passive"))
      (node (ref "LD4") (pin "2") (pinfunction "K_2") (pintype "passive"))
      (node (ref "P2") (pin "29") (pinfunction "29_29") (pintype "passive"))
      (node (ref "P2") (pin "30") (pinfunction "30_30") (pintype "passive"))
      (node (ref "P2") (pin "31") (pinfunction "31_31") (pintype "passive"))
      (node (ref "P2") (pin "32") (pinfunction "32_32") (pintype "passive"))
      (node (ref "R12") (pin "1") (pinfunction "1_1") (pintype "passive"))
      (node (ref "R20") (pin "1") (pinfunction "1_1") (pintype "passive"))
      (node (ref "R21") (pin "2") (pinfunction "2_2") (pintype "passive"))
      (node (ref "R22") (pin "1") (pinfunction "1_1") (pintype "passive"))
      (node (ref "R3") (pin "1") (pinfunction "1_1") (pintype "passive"))
      (node (ref "U1") (pin "15") (pinfunction "PAD_15") (pintype "passive"))
      (node (ref "U1") (pin "5") (pinfunction "GND_5") (pintype "passive"))
      (node (ref "U1") (pin "8") (pinfunction "PGND1_8") (pintype "passive"))
      (node (ref "U1") (pin "9") (pinfunction "PGND2_9") (pintype "passive"))
      (node (ref "U2") (pin "1") (pinfunction "A1_1") (pintype "passive"))
      (node (ref "U2") (pin "7") (pinfunction "GND_7") (pintype "passive"))
      (node (ref "U3") (pin "15") (pinfunction "PAD_15") (pintype "passive"))
      (node (ref "U3") (pin "5") (pinfunction "GND_5") (pintype "passive"))
      (node (ref "U3") (pin "8") (pinfunction "PGND1_8") (pintype "passive"))
      (node (ref "U3") (pin "9") (pinfunction "PGND2_9") (pintype "passive"))
      (node (ref "U4") (pin "1") (pinfunction "A1_1") (pintype "passive"))
      (node (ref "U4") (pin "2") (pinfunction "A0_2") (pintype "passive"))
      (node (ref "U4") (pin "7") (pinfunction "GND_7") (pintype "passive"))
      (node (ref "U5") (pin "2") (pinfunction "GND_2") (pintype "passive"))
      (node (ref "X1") (pin "2") (pinfunction "GND_2") (pintype "passive"))
    )
    (net (code "90") (name "Net-(C8-Pad2)") (class "Default")
      (node (ref "C8") (pin "2") (pinfunction "2_2") (pintype "passive"))
      (node (ref "C9") (pin "1") (pinfunction "1_1") (pintype "passive"))
    )
    (net (code "91") (name "Net-(C20-Pad1)") (class "Default")
      (node (ref "C20") (pin "1") (pinfunction "1_1") (pintype "passive"))
      (node (ref "C21") (pin "2") (pinfunction "2_2") (pintype "passive"))
    )
    (net (code "92") (name "Net-(JTAG-Pad6)") (class "Default")
      (node (ref "JTAG") (pin "6") (pinfunction "6_6") (pintype "passive"))
      (node (ref "JTAG") (pin "7") (pinfunction "7_7") (pintype "passive"))
      (node (ref "Pv") (pin "1") (pinfunction "1_1") (pintype "passive"))
    )
    (net (code "93") (name "Net-(LD1-A)") (class "Default")
      (node (ref "LD1") (pin "1") (pinfunction "A_1") (pintype "passive"))
      (node (ref "R25") (pin "2") (pinfunction "2_2") (pintype "passive"))
    )
    (net (code "94") (name "Net-(LD2-A)") (class "Default")
      (node (ref "LD2") (pin "1") (pinfunction "A_1") (pintype "passive"))
      (node (ref "R26") (pin "2") (pinfunction "2_2") (pintype "passive"))
    )
    (net (code "95") (name "Net-(LD3-A)") (class "Default")
      (node (ref "LD3") (pin "1") (pinfunction "A_1") (pintype "passive"))
      (node (ref "R27") (pin "2") (pinfunction "2_2") (pintype "passive"))
    )
    (net (code "96") (name "Net-(LD4-A)") (class "Default")
      (node (ref "LD4") (pin "1") (pinfunction "A_1") (pintype "passive"))
      (node (ref "R28") (pin "2") (pinfunction "2_2") (pintype "passive"))
    )
    (net (code "97") (name "Net-(U1-SS)") (class "Default")
      (node (ref "C4") (pin "2") (pinfunction "2_2") (pintype "passive"))
      (node (ref "U1") (pin "4") (pinfunction "SS_4") (pintype "passive"))
    )
    (net (code "98") (name "Net-(U1-SW1)") (class "Default")
      (node (ref "C5") (pin "1") (pinfunction "1_1") (pintype "passive"))
      (node (ref "L1") (pin "1") (pinfunction "1_1") (pintype "passive"))
      (node (ref "U1") (pin "10") (pinfunction "SW1_10") (pintype "passive"))
      (node (ref "U1") (pin "11") (pinfunction "SW2_11") (pintype "passive"))
    )
    (net (code "99") (name "Net-(U1-VBST)") (class "Default")
      (node (ref "C5") (pin "2") (pinfunction "2_2") (pintype "passive"))
      (node (ref "U1") (pin "12") (pinfunction "VBST_12") (pintype "passive"))
    )
    (net (code "100") (name "Net-(U1-VFB)") (class "Default")
      (node (ref "R3") (pin "2") (pinfunction "2_2") (pintype "passive"))
      (node (ref "R4") (pin "1") (pinfunction "1_1") (pintype "passive"))
      (node (ref "U1") (pin "2") (pinfunction "VFB_2") (pintype "passive"))
    )
    (net (code "101") (name "Net-(U1-VO)") (class "Default")
      (node (ref "C6") (pin "1") (pinfunction "1_1") (pintype "passive"))
      (node (ref "C7") (pin "1") (pinfunction "1_1") (pintype "passive"))
      (node (ref "L1") (pin "2") (pinfunction "2_2") (pintype "passive"))
      (node (ref "R4") (pin "2") (pinfunction "2_2") (pintype "passive"))
      (node (ref "R45") (pin "2") (pinfunction "2_2") (pintype "passive"))
      (node (ref "R5") (pin "2") (pinfunction "2_2") (pintype "passive"))
      (node (ref "R6") (pin "2") (pinfunction "2_2") (pintype "passive"))
      (node (ref "U1") (pin "1") (pinfunction "VO_1") (pintype "passive"))
    )
    (net (code "102") (name "Net-(U1-VREG5)") (class "Default")
      (node (ref "C3") (pin "2") (pinfunction "2_2") (pintype "passive"))
      (node (ref "R2") (pin "1") (pinfunction "1_1") (pintype "passive"))
      (node (ref "U1") (pin "3") (pinfunction "VREG5_3") (pintype "passive"))
    )
    (net (code "103") (name "Net-(U2-IN+)") (class "Default")
      (node (ref "C10") (pin "2") (pinfunction "2_2") (pintype "passive"))
      (node (ref "R6") (pin "1") (pinfunction "1_1") (pintype "passive"))
      (node (ref "U2") (pin "10") (pinfunction "IN+_10") (pintype "passive"))
      (node (ref "U2") (pin "8") (pinfunction "VBUS_8") (pintype "passive"))
    )
    (net (code "104") (name "Net-(U2-IN-)") (class "Default")
      (node (ref "C10") (pin "1") (pinfunction "1_1") (pintype "passive"))
      (node (ref "R7") (pin "1") (pinfunction "1_1") (pintype "passive"))
      (node (ref "U2") (pin "9") (pinfunction "IN-_9") (pintype "passive"))
    )
    (net (code "105") (name "Net-(U3-SS)") (class "Default")
      (node (ref "C15") (pin "2") (pinfunction "2_2") (pintype "passive"))
      (node (ref "U3") (pin "4") (pinfunction "SS_4") (pintype "passive"))
    )
    (net (code "106") (name "Net-(U3-SW1)") (class "Default")
      (node (ref "C16") (pin "1") (pinfunction "1_1") (pintype "passive"))
      (node (ref "L2") (pin "1") (pinfunction "1_1") (pintype "passive"))
      (node (ref "U3") (pin "10") (pinfunction "SW1_10") (pintype "passive"))
      (node (ref "U3") (pin "11") (pinfunction "SW2_11") (pintype "passive"))
    )
    (net (code "107") (name "Net-(U3-VBST)") (class "Default")
      (node (ref "C16") (pin "2") (pinfunction "2_2") (pintype "passive"))
      (node (ref "U3") (pin "12") (pinfunction "VBST_12") (pintype "passive"))
    )
    (net (code "108") (name "Net-(U3-VFB)") (class "Default")
      (node (ref "C17") (pin "1") (pinfunction "1_1") (pintype "passive"))
      (node (ref "R12") (pin "2") (pinfunction "2_2") (pintype "passive"))
      (node (ref "R13") (pin "1") (pinfunction "1_1") (pintype "passive"))
      (node (ref "U3") (pin "2") (pinfunction "VFB_2") (pintype "passive"))
    )
    (net (code "109") (name "Net-(U3-VO)") (class "Default")
      (node (ref "C17") (pin "2") (pinfunction "2_2") (pintype "passive"))
      (node (ref "C18") (pin "1") (pinfunction "1_1") (pintype "passive"))
      (node (ref "C19") (pin "1") (pinfunction "1_1") (pintype "passive"))
      (node (ref "L2") (pin "2") (pinfunction "2_2") (pintype "passive"))
      (node (ref "R13") (pin "2") (pinfunction "2_2") (pintype "passive"))
      (node (ref "R14") (pin "2") (pinfunction "2_2") (pintype "passive"))
      (node (ref "R16") (pin "2") (pinfunction "2_2") (pintype "passive"))
      (node (ref "R24") (pin "2") (pinfunction "2_2") (pintype "passive"))
      (node (ref "U3") (pin "1") (pinfunction "VO_1") (pintype "passive"))
    )
    (net (code "110") (name "Net-(U3-VREG5)") (class "Default")
      (node (ref "C14") (pin "2") (pinfunction "2_2") (pintype "passive"))
      (node (ref "R10") (pin "1") (pinfunction "1_1") (pintype "passive"))
      (node (ref "U3") (pin "3") (pinfunction "VREG5_3") (pintype "passive"))
    )
    (net (code "111") (name "Net-(U4-IN+)") (class "Default")
      (node (ref "C22") (pin "2") (pinfunction "2_2") (pintype "passive"))
      (node (ref "R14") (pin "1") (pinfunction "1_1") (pintype "passive"))
      (node (ref "U4") (pin "10") (pinfunction "IN+_10") (pintype "passive"))
      (node (ref "U4") (pin "8") (pinfunction "VBUS_8") (pintype "passive"))
    )
    (net (code "112") (name "Net-(U4-IN-)") (class "Default")
      (node (ref "C22") (pin "1") (pinfunction "1_1") (pintype "passive"))
      (node (ref "R15") (pin "1") (pinfunction "1_1") (pintype "passive"))
      (node (ref "U4") (pin "9") (pinfunction "IN-_9") (pintype "passive"))
    )
    (net (code "113") (name "Net-(U5-RS)") (class "Default")
      (node (ref "R22") (pin "2") (pinfunction "2_2") (pintype "passive"))
      (node (ref "U5") (pin "8") (pinfunction "RS_8") (pintype "passive"))
    )
    (net (code "114") (name "Net-(X1-OE{slash}_ST)") (class "Default")
      (node (ref "R19") (pin "2") (pinfunction "2_2") (pintype "passive"))
      (node (ref "X1") (pin "1") (pinfunction "OE/_ST_1") (pintype "passive"))
    )
    (net (code "115") (name "VCC_1V5") (class "Default")
      (node (ref "C8") (pin "1") (pinfunction "1_1") (pintype "passive"))
      (node (ref "F1") (pin "142") (pinfunction "VCC_142") (pintype "passive"))
      (node (ref "F1") (pin "16") (pinfunction "VCC_16") (pintype "power_in"))
      (node (ref "F1") (pin "171") (pinfunction "VCC_171") (pintype "power_in"))
      (node (ref "F1") (pin "187") (pinfunction "VCC_187") (pintype "power_in"))
      (node (ref "F1") (pin "27") (pinfunction "VCCPLF_27") (pintype "power_in"))
      (node (ref "F1") (pin "36") (pinfunction "VCC_36") (pintype "power_in"))
      (node (ref "F1") (pin "71") (pinfunction "VCC_71") (pintype "power_in"))
      (node (ref "F1") (pin "88") (pinfunction "VCC_88") (pintype "power_in"))
      (node (ref "R45") (pin "1") (pinfunction "1_1") (pintype "passive"))
      (node (ref "R5") (pin "1") (pinfunction "1_1") (pintype "passive"))
      (node (ref "R7") (pin "2") (pinfunction "2_2") (pintype "passive"))
    )
    (net (code "116") (name "VCC_3V3") (class "Default")
      (node (ref "C11") (pin "1") (pinfunction "1_1") (pintype "passive"))
      (node (ref "C21") (pin "1") (pinfunction "1_1") (pintype "passive"))
      (node (ref "C23") (pin "1") (pinfunction "1_1") (pintype "passive"))
      (node (ref "C24") (pin "1") (pinfunction "1_1") (pintype "passive"))
      (node (ref "C25") (pin "1") (pinfunction "1_1") (pintype "passive"))
      (node (ref "C26") (pin "1") (pinfunction "1_1") (pintype "passive"))
      (node (ref "F1") (pin "104") (pinfunction "VMV2_104") (pintype "power_in"))
      (node (ref "F1") (pin "106") (pinfunction "VPUMP_106") (pintype "power_in"))
      (node (ref "F1") (pin "110") (pinfunction "VJTAG_110") (pintype "power_in"))
      (node (ref "F1") (pin "123") (pinfunction "VCCIB1_123") (pintype "power_in"))
      (node (ref "F1") (pin "140") (pinfunction "VCCIB1_140") (pintype "passive"))
      (node (ref "F1") (pin "154") (pinfunction "VMV1_154") (pintype "passive"))
      (node (ref "F1") (pin "157") (pinfunction "VMV0_157") (pintype "power_in"))
      (node (ref "F1") (pin "170") (pinfunction "VCCIB0_170") (pintype "power_in"))
      (node (ref "F1") (pin "18") (pinfunction "VCCIB3_18") (pintype "power_in"))
      (node (ref "F1") (pin "186") (pinfunction "VCCIB0_186") (pintype "power_in"))
      (node (ref "F1") (pin "200") (pinfunction "VCCIB0_200") (pintype "power_in"))
      (node (ref "F1") (pin "208") (pinfunction "VMV0_208") (pintype "power_in"))
      (node (ref "F1") (pin "40") (pinfunction "VCCIB3_40") (pintype "power_in"))
      (node (ref "F1") (pin "50") (pinfunction "VMV3_50") (pintype "power_in"))
      (node (ref "F1") (pin "53") (pinfunction "VMV2_53") (pintype "power_in"))
      (node (ref "F1") (pin "62") (pinfunction "VCCIB2_62") (pintype "power_in"))
      (node (ref "F1") (pin "72") (pinfunction "VCCIB2_72") (pintype "power_in"))
      (node (ref "F1") (pin "89") (pinfunction "VCCIB2_89") (pintype "power_in"))
      (node (ref "Pv") (pin "2") (pinfunction "2_2") (pintype "passive"))
      (node (ref "R15") (pin "2") (pinfunction "2_2") (pintype "passive"))
      (node (ref "R16") (pin "1") (pinfunction "1_1") (pintype "passive"))
      (node (ref "R17") (pin "2") (pinfunction "2_2") (pintype "passive"))
      (node (ref "R18") (pin "2") (pinfunction "2_2") (pintype "passive"))
      (node (ref "R19") (pin "1") (pinfunction "1_1") (pintype "passive"))
      (node (ref "R24") (pin "1") (pinfunction "1_1") (pintype "passive"))
      (node (ref "R8") (pin "2") (pinfunction "2_2") (pintype "passive"))
      (node (ref "R9") (pin "2") (pinfunction "2_2") (pintype "passive"))
      (node (ref "U2") (pin "6") (pinfunction "VS_6") (pintype "passive"))
      (node (ref "U4") (pin "6") (pinfunction "VS_6") (pintype "passive"))
      (node (ref "X1") (pin "4") (pinfunction "VDD_4") (pintype "passive"))
    )
    (net (code "117") (name "VOUT_3V3") (class "Default")
      (node (ref "C27") (pin "1") (pinfunction "1_1") (pintype "passive"))
      (node (ref "P2") (pin "27") (pinfunction "27_27") (pintype "passive"))
      (node (ref "P2") (pin "28") (pinfunction "28_28") (pintype "passive"))
      (node (ref "U5") (pin "3") (pinfunction "VCC_3") (pintype "passive"))
    )
    (net (code "118") (name "VOUT_BATT") (class "Default")
      (node (ref "C1") (pin "1") (pinfunction "1_1") (pintype "passive"))
      (node (ref "C12") (pin "1") (pinfunction "1_1") (pintype "passive"))
      (node (ref "C13") (pin "1") (pinfunction "1_1") (pintype "passive"))
      (node (ref "C2") (pin "1") (pinfunction "1_1") (pintype "passive"))
      (node (ref "P2") (pin "45") (pinfunction "45_45") (pintype "passive"))
      (node (ref "P2") (pin "46") (pinfunction "46_46") (pintype "passive"))
      (node (ref "R1") (pin "2") (pinfunction "2_2") (pintype "passive"))
      (node (ref "R11") (pin "2") (pinfunction "2_2") (pintype "passive"))
      (node (ref "U1") (pin "13") (pinfunction "VIN_13") (pintype "passive"))
      (node (ref "U1") (pin "14") (pinfunction "VCC_14") (pintype "passive"))
      (node (ref "U3") (pin "13") (pinfunction "VIN_13") (pintype "passive"))
      (node (ref "U3") (pin "14") (pinfunction "VCC_14") (pintype "passive"))
    )
    (net (code "119") (name "unconnected-(F1-GAA2{slash}IO225PDB3-Pad2)") (class "Default")
      (node (ref "F1") (pin "2") (pinfunction "GAA2/IO225PDB3_2") (pintype "bidirectional"))
    )
    (net (code "120") (name "unconnected-(F1-GAB2{slash}IO224PDB3-Pad4)") (class "Default")
      (node (ref "F1") (pin "4") (pinfunction "GAB2/IO224PDB3_4") (pintype "bidirectional"))
    )
    (net (code "121") (name "unconnected-(F1-GBA0{slash}IO76RSB0-Pad159)") (class "Default")
      (node (ref "F1") (pin "159") (pinfunction "GBA0/IO76RSB0_159") (pintype "bidirectional"))
    )
    (net (code "122") (name "unconnected-(F1-GBB0{slash}IO74RSB0-Pad161)") (class "Default")
      (node (ref "F1") (pin "161") (pinfunction "GBB0/IO74RSB0_161") (pintype "bidirectional"))
    )
    (net (code "123") (name "unconnected-(F1-GBB1{slash}IO75RSB0-Pad160)") (class "Default")
      (node (ref "F1") (pin "160") (pinfunction "GBB1/IO75RSB0_160") (pintype "bidirectional"))
    )
    (net (code "124") (name "unconnected-(F1-GBC0{slash}IO72RSB0-Pad164)") (class "Default")
      (node (ref "F1") (pin "164") (pinfunction "GBC0/IO72RSB0_164") (pintype "bidirectional"))
    )
    (net (code "125") (name "unconnected-(F1-GBC1{slash}IO73RSB0-Pad163)") (class "Default")
      (node (ref "F1") (pin "163") (pinfunction "GBC1/IO73RSB0_163") (pintype "bidirectional"))
    )
    (net (code "126") (name "unconnected-(F1-GDA0{slash}IO113NDB1-Pad111)") (class "Default")
      (node (ref "F1") (pin "111") (pinfunction "GDA0/IO113NDB1_111") (pintype "power_in"))
    )
    (net (code "127") (name "unconnected-(F1-GDA1{slash}IO113PDB1-Pad112)") (class "Default")
      (node (ref "F1") (pin "112") (pinfunction "GDA1/IO113PDB1_112") (pintype "power_in"))
    )
    (net (code "128") (name "unconnected-(F1-GDA2{slash}IO114RSB2-Pad99)") (class "Default")
      (node (ref "F1") (pin "99") (pinfunction "GDA2/IO114RSB2_99") (pintype "bidirectional"))
    )
    (net (code "129") (name "unconnected-(F1-GDB0{slash}IO112NDB1-Pad113)") (class "Default")
      (node (ref "F1") (pin "113") (pinfunction "GDB0/IO112NDB1_113") (pintype "power_in"))
    )
    (net (code "130") (name "unconnected-(F1-GDB1{slash}IO112PDB1-Pad114)") (class "Default")
      (node (ref "F1") (pin "114") (pinfunction "GDB1/IO112PDB1_114") (pintype "power_in"))
    )
    (net (code "131") (name "unconnected-(F1-GDB2{slash}IO115RSB2-Pad98)") (class "Default")
      (node (ref "F1") (pin "98") (pinfunction "GDB2/IO115RSB2_98") (pintype "bidirectional"))
    )
    (net (code "132") (name "unconnected-(F1-GDC2{slash}IO116RSB2-Pad96)") (class "Default")
      (node (ref "F1") (pin "96") (pinfunction "GDC2/IO116RSB2_96") (pintype "bidirectional"))
    )
    (net (code "133") (name "unconnected-(F1-GEA0{slash}IO188NDB3-Pad49)") (class "Default")
      (node (ref "F1") (pin "49") (pinfunction "GEA0/IO188NDB3_49") (pintype "bidirectional"))
    )
    (net (code "134") (name "unconnected-(F1-GEA1{slash}IO188PDB3-Pad48)") (class "Default")
      (node (ref "F1") (pin "48") (pinfunction "GEA1/IO188PDB3_48") (pintype "bidirectional"))
    )
    (net (code "135") (name "unconnected-(F1-GEA2{slash}IO187RSB2-Pad54)") (class "Default")
      (node (ref "F1") (pin "54") (pinfunction "GEA2/IO187RSB2_54") (pintype "bidirectional"))
    )
    (net (code "136") (name "unconnected-(F1-GEB0{slash}IO189NDB3-Pad47)") (class "Default")
      (node (ref "F1") (pin "47") (pinfunction "GEB0/IO189NDB3_47") (pintype "bidirectional"))
    )
    (net (code "137") (name "unconnected-(F1-GEB2{slash}IO186RSB2-Pad55)") (class "Default")
      (node (ref "F1") (pin "55") (pinfunction "GEB2/IO186RSB2_55") (pintype "bidirectional"))
    )
    (net (code "138") (name "unconnected-(F1-GEC2{slash}IO185RSB2-Pad56)") (class "Default")
      (node (ref "F1") (pin "56") (pinfunction "GEC2/IO185RSB2_56") (pintype "bidirectional"))
    )
    (net (code "139") (name "unconnected-(F1-GFA0{slash}IO207NPB3-Pad26)") (class "Default")
      (node (ref "F1") (pin "26") (pinfunction "GFA0/IO207NPB3_26") (pintype "bidirectional"))
    )
    (net (code "140") (name "unconnected-(F1-GFA1{slash}IO207PPB3-Pad28)") (class "Default")
      (node (ref "F1") (pin "28") (pinfunction "GFA1/IO207PPB3_28") (pintype "bidirectional"))
    )
    (net (code "141") (name "unconnected-(F1-GFB0{slash}IO208NDB3-Pad24)") (class "Default")
      (node (ref "F1") (pin "24") (pinfunction "GFB0/IO208NDB3_24") (pintype "bidirectional"))
    )
    (net (code "142") (name "unconnected-(F1-GFB1{slash}IO208PDB3-Pad23)") (class "Default")
      (node (ref "F1") (pin "23") (pinfunction "GFB1/IO208PDB3_23") (pintype "bidirectional"))
    )
    (net (code "143") (name "unconnected-(F1-GFC0{slash}IO209NDB3-Pad22)") (class "Default")
      (node (ref "F1") (pin "22") (pinfunction "GFC0/IO209NDB3_22") (pintype "bidirectional"))
    )
    (net (code "144") (name "unconnected-(F1-GFC1{slash}IO209PDB3-Pad21)") (class "Default")
      (node (ref "F1") (pin "21") (pinfunction "GFC1/IO209PDB3_21") (pintype "bidirectional"))
    )
    (net (code "145") (name "unconnected-(F1-IO40RSB0-Pad177)") (class "Default")
      (node (ref "F1") (pin "177") (pinfunction "IO40RSB0_177") (pintype "bidirectional"))
    )
    (net (code "146") (name "unconnected-(F1-IO42RSB0-Pad176)") (class "Default")
      (node (ref "F1") (pin "176") (pinfunction "IO42RSB0_176") (pintype "bidirectional"))
    )
    (net (code "147") (name "unconnected-(F1-IO45RSB0-Pad175)") (class "Default")
      (node (ref "F1") (pin "175") (pinfunction "IO45RSB0_175") (pintype "bidirectional"))
    )
    (net (code "148") (name "unconnected-(F1-IO48RSB0-Pad174)") (class "Default")
      (node (ref "F1") (pin "174") (pinfunction "IO48RSB0_174") (pintype "bidirectional"))
    )
    (net (code "149") (name "unconnected-(F1-IO51RSB0-Pad173)") (class "Default")
      (node (ref "F1") (pin "173") (pinfunction "IO51RSB0_173") (pintype "bidirectional"))
    )
    (net (code "150") (name "unconnected-(F1-IO54RSB0-Pad172)") (class "Default")
      (node (ref "F1") (pin "172") (pinfunction "IO54RSB0_172") (pintype "bidirectional"))
    )
    (net (code "151") (name "unconnected-(F1-IO57RSB0-Pad169)") (class "Default")
      (node (ref "F1") (pin "169") (pinfunction "IO57RSB0_169") (pintype "bidirectional"))
    )
    (net (code "152") (name "unconnected-(F1-IO60RSB0-Pad168)") (class "Default")
      (node (ref "F1") (pin "168") (pinfunction "IO60RSB0_168") (pintype "bidirectional"))
    )
    (net (code "153") (name "unconnected-(F1-IO63RSB0-Pad167)") (class "Default")
      (node (ref "F1") (pin "167") (pinfunction "IO63RSB0_167") (pintype "bidirectional"))
    )
    (net (code "154") (name "unconnected-(F1-IO67RSB0-Pad166)") (class "Default")
      (node (ref "F1") (pin "166") (pinfunction "IO67RSB0_166") (pintype "bidirectional"))
    )
    (net (code "155") (name "unconnected-(F1-IO70RSB0-Pad165)") (class "Default")
      (node (ref "F1") (pin "165") (pinfunction "IO70RSB0_165") (pintype "bidirectional"))
    )
    (net (code "156") (name "unconnected-(F1-IO88PDB1-Pad139)") (class "Default")
      (node (ref "F1") (pin "139") (pinfunction "IO88PDB1_139") (pintype "power_in"))
    )
    (net (code "157") (name "unconnected-(F1-IO104PSB1-Pad121)") (class "Default")
      (node (ref "F1") (pin "121") (pinfunction "IO104PSB1_121") (pintype "power_in"))
    )
    (net (code "158") (name "unconnected-(F1-IO118RSB2-Pad95)") (class "Default")
      (node (ref "F1") (pin "95") (pinfunction "IO118RSB2_95") (pintype "bidirectional"))
    )
    (net (code "159") (name "unconnected-(F1-IO120RSB2-Pad94)") (class "Default")
      (node (ref "F1") (pin "94") (pinfunction "IO120RSB2_94") (pintype "bidirectional"))
    )
    (net (code "160") (name "unconnected-(F1-IO122RSB2-Pad93)") (class "Default")
      (node (ref "F1") (pin "93") (pinfunction "IO122RSB2_93") (pintype "bidirectional"))
    )
    (net (code "161") (name "unconnected-(F1-IO124RSB2-Pad92)") (class "Default")
      (node (ref "F1") (pin "92") (pinfunction "IO124RSB2_92") (pintype "bidirectional"))
    )
    (net (code "162") (name "unconnected-(F1-IO126RSB2-Pad91)") (class "Default")
      (node (ref "F1") (pin "91") (pinfunction "IO126RSB2_91") (pintype "bidirectional"))
    )
    (net (code "163") (name "unconnected-(F1-IO128RSB2-Pad90)") (class "Default")
      (node (ref "F1") (pin "90") (pinfunction "IO128RSB2_90") (pintype "bidirectional"))
    )
    (net (code "164") (name "unconnected-(F1-IO139RSB2-Pad84)") (class "Default")
      (node (ref "F1") (pin "84") (pinfunction "IO139RSB2_84") (pintype "bidirectional"))
    )
    (net (code "165") (name "unconnected-(F1-IO141RSB2-Pad83)") (class "Default")
      (node (ref "F1") (pin "83") (pinfunction "IO141RSB2_83") (pintype "bidirectional"))
    )
    (net (code "166") (name "unconnected-(F1-IO143RSB2-Pad82)") (class "Default")
      (node (ref "F1") (pin "82") (pinfunction "IO143RSB2_82") (pintype "bidirectional"))
    )
    (net (code "167") (name "unconnected-(F1-IO150RSB2-Pad79)") (class "Default")
      (node (ref "F1") (pin "79") (pinfunction "IO150RSB2_79") (pintype "bidirectional"))
    )
    (net (code "168") (name "unconnected-(F1-IO152RSB2-Pad78)") (class "Default")
      (node (ref "F1") (pin "78") (pinfunction "IO152RSB2_78") (pintype "bidirectional"))
    )
    (net (code "169") (name "unconnected-(F1-IO154RSB2-Pad77)") (class "Default")
      (node (ref "F1") (pin "77") (pinfunction "IO154RSB2_77") (pintype "bidirectional"))
    )
    (net (code "170") (name "unconnected-(F1-IO156RSB2-Pad76)") (class "Default")
      (node (ref "F1") (pin "76") (pinfunction "IO156RSB2_76") (pintype "bidirectional"))
    )
    (net (code "171") (name "unconnected-(F1-IO158RSB2-Pad75)") (class "Default")
      (node (ref "F1") (pin "75") (pinfunction "IO158RSB2_75") (pintype "bidirectional"))
    )
    (net (code "172") (name "unconnected-(F1-IO160RSB2-Pad74)") (class "Default")
      (node (ref "F1") (pin "74") (pinfunction "IO160RSB2_74") (pintype "bidirectional"))
    )
    (net (code "173") (name "unconnected-(F1-IO162RSB2-Pad73)") (class "Default")
      (node (ref "F1") (pin "73") (pinfunction "IO162RSB2_73") (pintype "bidirectional"))
    )
    (net (code "174") (name "unconnected-(F1-IO166RSB2-Pad70)") (class "Default")
      (node (ref "F1") (pin "70") (pinfunction "IO166RSB2_70") (pintype "bidirectional"))
    )
    (net (code "175") (name "unconnected-(F1-IO168RSB2-Pad69)") (class "Default")
      (node (ref "F1") (pin "69") (pinfunction "IO168RSB2_69") (pintype "bidirectional"))
    )
    (net (code "176") (name "unconnected-(F1-IO170RSB2-Pad68)") (class "Default")
      (node (ref "F1") (pin "68") (pinfunction "IO170RSB2_68") (pintype "bidirectional"))
    )
    (net (code "177") (name "unconnected-(F1-IO172RSB2-Pad67)") (class "Default")
      (node (ref "F1") (pin "67") (pinfunction "IO172RSB2_67") (pintype "bidirectional"))
    )
    (net (code "178") (name "unconnected-(F1-IO174RSB2-Pad66)") (class "Default")
      (node (ref "F1") (pin "66") (pinfunction "IO174RSB2_66") (pintype "bidirectional"))
    )
    (net (code "179") (name "unconnected-(F1-IO176RSB2-Pad64)") (class "Default")
      (node (ref "F1") (pin "64") (pinfunction "IO176RSB2_64") (pintype "bidirectional"))
    )
    (net (code "180") (name "unconnected-(F1-IO178RSB2-Pad63)") (class "Default")
      (node (ref "F1") (pin "63") (pinfunction "IO178RSB2_63") (pintype "bidirectional"))
    )
    (net (code "181") (name "unconnected-(F1-IO180RSB2-Pad61)") (class "Default")
      (node (ref "F1") (pin "61") (pinfunction "IO180RSB2_61") (pintype "bidirectional"))
    )
    (net (code "182") (name "unconnected-(F1-IO181RSB2-Pad60)") (class "Default")
      (node (ref "F1") (pin "60") (pinfunction "IO181RSB2_60") (pintype "bidirectional"))
    )
    (net (code "183") (name "unconnected-(F1-IO182RSB2-Pad59)") (class "Default")
      (node (ref "F1") (pin "59") (pinfunction "IO182RSB2_59") (pintype "bidirectional"))
    )
    (net (code "184") (name "unconnected-(F1-IO183RSB2-Pad58)") (class "Default")
      (node (ref "F1") (pin "58") (pinfunction "IO183RSB2_58") (pintype "bidirectional"))
    )
    (net (code "185") (name "unconnected-(F1-IO184RSB2-Pad57)") (class "Default")
      (node (ref "F1") (pin "57") (pinfunction "IO184RSB2_57") (pintype "bidirectional"))
    )
    (net (code "186") (name "unconnected-(F1-IO191PDB3-Pad42)") (class "Default")
      (node (ref "F1") (pin "42") (pinfunction "IO191PDB3_42") (pintype "bidirectional"))
    )
    (net (code "187") (name "unconnected-(F1-IO212NDB3-Pad20)") (class "Default")
      (node (ref "F1") (pin "20") (pinfunction "IO212NDB3_20") (pintype "bidirectional"))
    )
    (net (code "188") (name "unconnected-(F1-IO212PDB3-Pad19)") (class "Default")
      (node (ref "F1") (pin "19") (pinfunction "IO212PDB3_19") (pintype "bidirectional"))
    )
    (net (code "189") (name "unconnected-(F1-IO216NDB3-Pad15)") (class "Default")
      (node (ref "F1") (pin "15") (pinfunction "IO216NDB3_15") (pintype "bidirectional"))
    )
    (net (code "190") (name "unconnected-(F1-IO216PDB3-Pad14)") (class "Default")
      (node (ref "F1") (pin "14") (pinfunction "IO216PDB3_14") (pintype "bidirectional"))
    )
    (net (code "191") (name "unconnected-(F1-IO218NDB3-Pad13)") (class "Default")
      (node (ref "F1") (pin "13") (pinfunction "IO218NDB3_13") (pintype "bidirectional"))
    )
    (net (code "192") (name "unconnected-(F1-IO218PDB3-Pad12)") (class "Default")
      (node (ref "F1") (pin "12") (pinfunction "IO218PDB3_12") (pintype "bidirectional"))
    )
    (net (code "193") (name "unconnected-(F1-IO224NDB3-Pad5)") (class "Default")
      (node (ref "F1") (pin "5") (pinfunction "IO224NDB3_5") (pintype "bidirectional"))
    )
    (net (code "194") (name "unconnected-(F1-IO225NDB3-Pad3)") (class "Default")
      (node (ref "F1") (pin "3") (pinfunction "IO225NDB3_3") (pintype "bidirectional"))
    )
    (net (code "195") (name "unconnected-(F1-NC-Pad126)") (class "Default")
      (node (ref "F1") (pin "126") (pinfunction "NC_126") (pintype "passive+no_connect"))
    )
    (net (code "196") (name "unconnected-(JTAG-Pad4)") (class "Default")
      (node (ref "JTAG") (pin "4") (pinfunction "4_4") (pintype "passive+no_connect"))
    )
    (net (code "197") (name "unconnected-(JTAG-Pad10)") (class "Default")
      (node (ref "JTAG") (pin "10") (pinfunction "10_10") (pintype "passive"))
    )
    (net (code "198") (name "unconnected-(P1-Pad2)") (class "Default")
      (node (ref "P1") (pin "2") (pinfunction "2_2") (pintype "passive"))
    )
    (net (code "199") (name "unconnected-(P1-Pad4)") (class "Default")
      (node (ref "P1") (pin "4") (pinfunction "4_4") (pintype "passive"))
    )
    (net (code "200") (name "unconnected-(P1-Pad5)") (class "Default")
      (node (ref "P1") (pin "5") (pinfunction "5_5") (pintype "passive"))
    )
    (net (code "201") (name "unconnected-(P1-Pad6)") (class "Default")
      (node (ref "P1") (pin "6") (pinfunction "6_6") (pintype "passive"))
    )
    (net (code "202") (name "unconnected-(P1-Pad7)") (class "Default")
      (node (ref "P1") (pin "7") (pinfunction "7_7") (pintype "passive"))
    )
    (net (code "203") (name "unconnected-(P1-Pad8)") (class "Default")
      (node (ref "P1") (pin "8") (pinfunction "8_8") (pintype "passive"))
    )
    (net (code "204") (name "unconnected-(P1-Pad9)") (class "Default")
      (node (ref "P1") (pin "9") (pinfunction "9_9") (pintype "passive"))
    )
    (net (code "205") (name "unconnected-(P1-Pad10)") (class "Default")
      (node (ref "P1") (pin "10") (pinfunction "10_10") (pintype "passive"))
    )
    (net (code "206") (name "unconnected-(P1-Pad11)") (class "Default")
      (node (ref "P1") (pin "11") (pinfunction "11_11") (pintype "passive"))
    )
    (net (code "207") (name "unconnected-(P1-Pad12)") (class "Default")
      (node (ref "P1") (pin "12") (pinfunction "12_12") (pintype "passive"))
    )
    (net (code "208") (name "unconnected-(P1-Pad13)") (class "Default")
      (node (ref "P1") (pin "13") (pinfunction "13_13") (pintype "passive"))
    )
    (net (code "209") (name "unconnected-(P1-Pad14)") (class "Default")
      (node (ref "P1") (pin "14") (pinfunction "14_14") (pintype "passive"))
    )
    (net (code "210") (name "unconnected-(P1-Pad15)") (class "Default")
      (node (ref "P1") (pin "15") (pinfunction "15_15") (pintype "passive"))
    )
    (net (code "211") (name "unconnected-(P1-Pad16)") (class "Default")
      (node (ref "P1") (pin "16") (pinfunction "16_16") (pintype "passive"))
    )
    (net (code "212") (name "unconnected-(P1-Pad17)") (class "Default")
      (node (ref "P1") (pin "17") (pinfunction "17_17") (pintype "passive"))
    )
    (net (code "213") (name "unconnected-(P1-Pad18)") (class "Default")
      (node (ref "P1") (pin "18") (pinfunction "18_18") (pintype "passive"))
    )
    (net (code "214") (name "unconnected-(P1-Pad19)") (class "Default")
      (node (ref "P1") (pin "19") (pinfunction "19_19") (pintype "passive"))
    )
    (net (code "215") (name "unconnected-(P1-Pad20)") (class "Default")
      (node (ref "P1") (pin "20") (pinfunction "20_20") (pintype "passive"))
    )
    (net (code "216") (name "unconnected-(P1-Pad21)") (class "Default")
      (node (ref "P1") (pin "21") (pinfunction "21_21") (pintype "passive"))
    )
    (net (code "217") (name "unconnected-(P1-Pad22)") (class "Default")
      (node (ref "P1") (pin "22") (pinfunction "22_22") (pintype "passive"))
    )
    (net (code "218") (name "unconnected-(P1-Pad23)") (class "Default")
      (node (ref "P1") (pin "23") (pinfunction "23_23") (pintype "passive"))
    )
    (net (code "219") (name "unconnected-(P1-Pad24)") (class "Default")
      (node (ref "P1") (pin "24") (pinfunction "24_24") (pintype "passive"))
    )
    (net (code "220") (name "unconnected-(P1-Pad25)") (class "Default")
      (node (ref "P1") (pin "25") (pinfunction "25_25") (pintype "passive"))
    )
    (net (code "221") (name "unconnected-(P1-Pad26)") (class "Default")
      (node (ref "P1") (pin "26") (pinfunction "26_26") (pintype "passive"))
    )
    (net (code "222") (name "unconnected-(P1-Pad27)") (class "Default")
      (node (ref "P1") (pin "27") (pinfunction "27_27") (pintype "passive"))
    )
    (net (code "223") (name "unconnected-(P1-Pad28)") (class "Default")
      (node (ref "P1") (pin "28") (pinfunction "28_28") (pintype "passive"))
    )
    (net (code "224") (name "unconnected-(P1-Pad29)") (class "Default")
      (node (ref "P1") (pin "29") (pinfunction "29_29") (pintype "passive"))
    )
    (net (code "225") (name "unconnected-(P1-Pad30)") (class "Default")
      (node (ref "P1") (pin "30") (pinfunction "30_30") (pintype "passive"))
    )
    (net (code "226") (name "unconnected-(P1-Pad31)") (class "Default")
      (node (ref "P1") (pin "31") (pinfunction "31_31") (pintype "passive"))
    )
    (net (code "227") (name "unconnected-(P1-Pad32)") (class "Default")
      (node (ref "P1") (pin "32") (pinfunction "32_32") (pintype "passive"))
    )
    (net (code "228") (name "unconnected-(P1-Pad33)") (class "Default")
      (node (ref "P1") (pin "33") (pinfunction "33_33") (pintype "passive"))
    )
    (net (code "229") (name "unconnected-(P1-Pad34)") (class "Default")
      (node (ref "P1") (pin "34") (pinfunction "34_34") (pintype "passive"))
    )
    (net (code "230") (name "unconnected-(P1-Pad35)") (class "Default")
      (node (ref "P1") (pin "35") (pinfunction "35_35") (pintype "passive"))
    )
    (net (code "231") (name "unconnected-(P1-Pad36)") (class "Default")
      (node (ref "P1") (pin "36") (pinfunction "36_36") (pintype "passive"))
    )
    (net (code "232") (name "unconnected-(P1-Pad37)") (class "Default")
      (node (ref "P1") (pin "37") (pinfunction "37_37") (pintype "passive"))
    )
    (net (code "233") (name "unconnected-(P1-Pad38)") (class "Default")
      (node (ref "P1") (pin "38") (pinfunction "38_38") (pintype "passive"))
    )
    (net (code "234") (name "unconnected-(P1-Pad39)") (class "Default")
      (node (ref "P1") (pin "39") (pinfunction "39_39") (pintype "passive"))
    )
    (net (code "235") (name "unconnected-(P1-Pad40)") (class "Default")
      (node (ref "P1") (pin "40") (pinfunction "40_40") (pintype "passive"))
    )
    (net (code "236") (name "unconnected-(P1-Pad41)") (class "Default")
      (node (ref "P1") (pin "41") (pinfunction "41_41") (pintype "passive"))
    )
    (net (code "237") (name "unconnected-(P1-Pad42)") (class "Default")
      (node (ref "P1") (pin "42") (pinfunction "42_42") (pintype "passive"))
    )
    (net (code "238") (name "unconnected-(P1-Pad43)") (class "Default")
      (node (ref "P1") (pin "43") (pinfunction "43_43") (pintype "passive"))
    )
    (net (code "239") (name "unconnected-(P1-Pad44)") (class "Default")
      (node (ref "P1") (pin "44") (pinfunction "44_44") (pintype "passive"))
    )
    (net (code "240") (name "unconnected-(P1-Pad45)") (class "Default")
      (node (ref "P1") (pin "45") (pinfunction "45_45") (pintype "passive"))
    )
    (net (code "241") (name "unconnected-(P1-Pad46)") (class "Default")
      (node (ref "P1") (pin "46") (pinfunction "46_46") (pintype "passive"))
    )
    (net (code "242") (name "unconnected-(P1-Pad47)") (class "Default")
      (node (ref "P1") (pin "47") (pinfunction "47_47") (pintype "passive"))
    )
    (net (code "243") (name "unconnected-(P1-Pad48)") (class "Default")
      (node (ref "P1") (pin "48") (pinfunction "48_48") (pintype "passive"))
    )
    (net (code "244") (name "unconnected-(P1-Pad49)") (class "Default")
      (node (ref "P1") (pin "49") (pinfunction "49_49") (pintype "passive"))
    )
    (net (code "245") (name "unconnected-(P1-Pad50)") (class "Default")
      (node (ref "P1") (pin "50") (pinfunction "50_50") (pintype "passive"))
    )
    (net (code "246") (name "unconnected-(P1-Pad51)") (class "Default")
      (node (ref "P1") (pin "51") (pinfunction "51_51") (pintype "passive"))
    )
    (net (code "247") (name "unconnected-(P1-Pad52)") (class "Default")
      (node (ref "P1") (pin "52") (pinfunction "52_52") (pintype "passive"))
    )
    (net (code "248") (name "unconnected-(P2-Pad1)") (class "Default")
      (node (ref "P2") (pin "1") (pinfunction "1_1") (pintype "passive"))
    )
    (net (code "249") (name "unconnected-(P2-Pad2)") (class "Default")
      (node (ref "P2") (pin "2") (pinfunction "2_2") (pintype "passive"))
    )
    (net (code "250") (name "unconnected-(P2-Pad3)") (class "Default")
      (node (ref "P2") (pin "3") (pinfunction "3_3") (pintype "passive"))
    )
    (net (code "251") (name "unconnected-(P2-Pad4)") (class "Default")
      (node (ref "P2") (pin "4") (pinfunction "4_4") (pintype "passive"))
    )
    (net (code "252") (name "unconnected-(P2-Pad5)") (class "Default")
      (node (ref "P2") (pin "5") (pinfunction "5_5") (pintype "passive"))
    )
    (net (code "253") (name "unconnected-(P2-Pad6)") (class "Default")
      (node (ref "P2") (pin "6") (pinfunction "6_6") (pintype "passive"))
    )
    (net (code "254") (name "unconnected-(P2-Pad7)") (class "Default")
      (node (ref "P2") (pin "7") (pinfunction "7_7") (pintype "passive"))
    )
    (net (code "255") (name "unconnected-(P2-Pad8)") (class "Default")
      (node (ref "P2") (pin "8") (pinfunction "8_8") (pintype "passive"))
    )
    (net (code "256") (name "unconnected-(P2-Pad9)") (class "Default")
      (node (ref "P2") (pin "9") (pinfunction "9_9") (pintype "passive"))
    )
    (net (code "257") (name "unconnected-(P2-Pad10)") (class "Default")
      (node (ref "P2") (pin "10") (pinfunction "10_10") (pintype "passive"))
    )
    (net (code "258") (name "unconnected-(P2-Pad11)") (class "Default")
      (node (ref "P2") (pin "11") (pinfunction "11_11") (pintype "passive"))
    )
    (net (code "259") (name "unconnected-(P2-Pad12)") (class "Default")
      (node (ref "P2") (pin "12") (pinfunction "12_12") (pintype "passive"))
    )
    (net (code "260") (name "unconnected-(P2-Pad13)") (class "Default")
      (node (ref "P2") (pin "13") (pinfunction "13_13") (pintype "passive"))
    )
    (net (code "261") (name "unconnected-(P2-Pad14)") (class "Default")
      (node (ref "P2") (pin "14") (pinfunction "14_14") (pintype "passive"))
    )
    (net (code "262") (name "unconnected-(P2-Pad15)") (class "Default")
      (node (ref "P2") (pin "15") (pinfunction "15_15") (pintype "passive"))
    )
    (net (code "263") (name "unconnected-(P2-Pad16)") (class "Default")
      (node (ref "P2") (pin "16") (pinfunction "16_16") (pintype "passive"))
    )
    (net (code "264") (name "unconnected-(P2-Pad17)") (class "Default")
      (node (ref "P2") (pin "17") (pinfunction "17_17") (pintype "passive"))
    )
    (net (code "265") (name "unconnected-(P2-Pad18)") (class "Default")
      (node (ref "P2") (pin "18") (pinfunction "18_18") (pintype "passive"))
    )
    (net (code "266") (name "unconnected-(P2-Pad19)") (class "Default")
      (node (ref "P2") (pin "19") (pinfunction "19_19") (pintype "passive"))
    )
    (net (code "267") (name "unconnected-(P2-Pad20)") (class "Default")
      (node (ref "P2") (pin "20") (pinfunction "20_20") (pintype "passive"))
    )
    (net (code "268") (name "unconnected-(P2-Pad21)") (class "Default")
      (node (ref "P2") (pin "21") (pinfunction "21_21") (pintype "passive"))
    )
    (net (code "269") (name "unconnected-(P2-Pad22)") (class "Default")
      (node (ref "P2") (pin "22") (pinfunction "22_22") (pintype "passive"))
    )
    (net (code "270") (name "unconnected-(P2-Pad23)") (class "Default")
      (node (ref "P2") (pin "23") (pinfunction "23_23") (pintype "passive"))
    )
    (net (code "271") (name "unconnected-(P2-Pad24)") (class "Default")
      (node (ref "P2") (pin "24") (pinfunction "24_24") (pintype "passive"))
    )
    (net (code "272") (name "unconnected-(P2-Pad33)") (class "Default")
      (node (ref "P2") (pin "33") (pinfunction "33_33") (pintype "passive"))
    )
    (net (code "273") (name "unconnected-(P2-Pad34)") (class "Default")
      (node (ref "P2") (pin "34") (pinfunction "34_34") (pintype "passive"))
    )
    (net (code "274") (name "unconnected-(P2-Pad35)") (class "Default")
      (node (ref "P2") (pin "35") (pinfunction "35_35") (pintype "passive"))
    )
    (net (code "275") (name "unconnected-(P2-Pad36)") (class "Default")
      (node (ref "P2") (pin "36") (pinfunction "36_36") (pintype "passive"))
    )
    (net (code "276") (name "unconnected-(P2-Pad37)") (class "Default")
      (node (ref "P2") (pin "37") (pinfunction "37_37") (pintype "passive"))
    )
    (net (code "277") (name "unconnected-(P2-Pad38)") (class "Default")
      (node (ref "P2") (pin "38") (pinfunction "38_38") (pintype "passive"))
    )
    (net (code "278") (name "unconnected-(P2-Pad39)") (class "Default")
      (node (ref "P2") (pin "39") (pinfunction "39_39") (pintype "passive"))
    )
    (net (code "279") (name "unconnected-(P2-Pad40)") (class "Default")
      (node (ref "P2") (pin "40") (pinfunction "40_40") (pintype "passive"))
    )
    (net (code "280") (name "unconnected-(P2-Pad41)") (class "Default")
      (node (ref "P2") (pin "41") (pinfunction "41_41") (pintype "passive"))
    )
    (net (code "281") (name "unconnected-(P2-Pad42)") (class "Default")
      (node (ref "P2") (pin "42") (pinfunction "42_42") (pintype "passive"))
    )
    (net (code "282") (name "unconnected-(P2-Pad43)") (class "Default")
      (node (ref "P2") (pin "43") (pinfunction "43_43") (pintype "passive"))
    )
    (net (code "283") (name "unconnected-(P2-Pad44)") (class "Default")
      (node (ref "P2") (pin "44") (pinfunction "44_44") (pintype "passive"))
    )
    (net (code "284") (name "unconnected-(P2-Pad47)") (class "Default")
      (node (ref "P2") (pin "47") (pinfunction "47_47") (pintype "passive"))
    )
    (net (code "285") (name "unconnected-(P2-Pad48)") (class "Default")
      (node (ref "P2") (pin "48") (pinfunction "48_48") (pintype "passive"))
    )
    (net (code "286") (name "unconnected-(P2-Pad49)") (class "Default")
      (node (ref "P2") (pin "49") (pinfunction "49_49") (pintype "passive"))
    )
    (net (code "287") (name "unconnected-(P2-Pad50)") (class "Default")
      (node (ref "P2") (pin "50") (pinfunction "50_50") (pintype "passive"))
    )
    (net (code "288") (name "unconnected-(P2-Pad51)") (class "Default")
      (node (ref "P2") (pin "51") (pinfunction "51_51") (pintype "passive"))
    )
    (net (code "289") (name "unconnected-(P2-Pad52)") (class "Default")
      (node (ref "P2") (pin "52") (pinfunction "52_52") (pintype "passive"))
    )
    (net (code "290") (name "unconnected-(U2-NC-Pad3)") (class "Default")
      (node (ref "U2") (pin "3") (pinfunction "NC_3") (pintype "passive"))
    )
    (net (code "291") (name "unconnected-(U4-NC-Pad3)") (class "Default")
      (node (ref "U4") (pin "3") (pinfunction "NC_3") (pintype "passive"))
    )
  )
)
